# ESP-RC-Car_NEW.net
KiCad netlist of a schematic drawn in Altium Designer
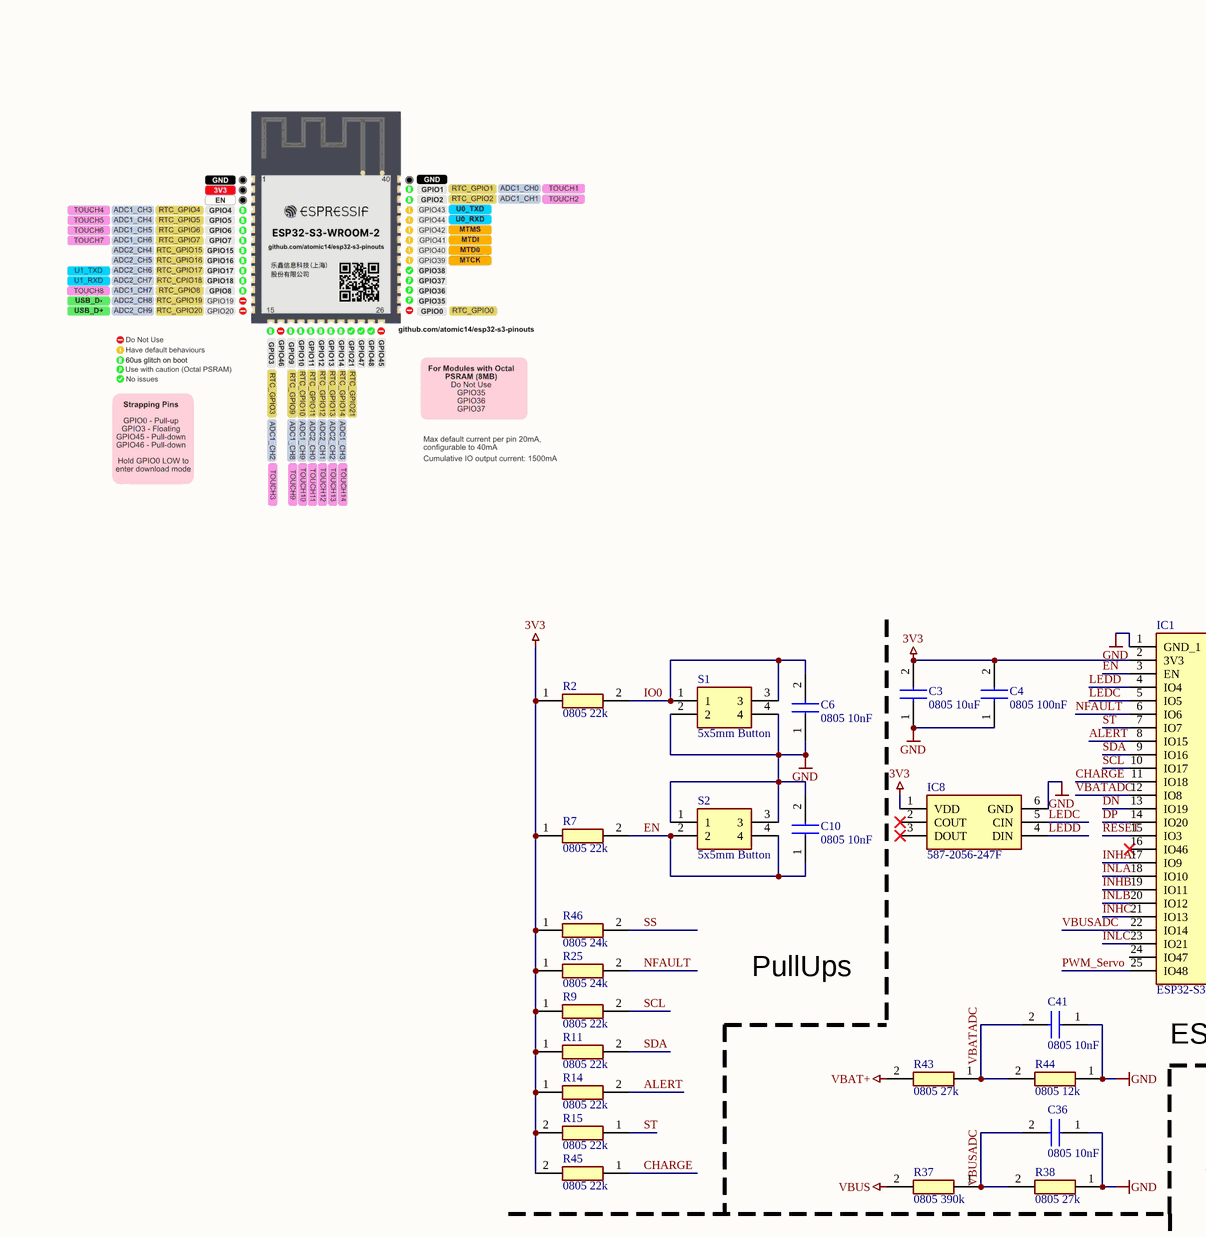
[diagram p0: ESP-RC-Car_NEW.SchDoc, top column 1 of 4]
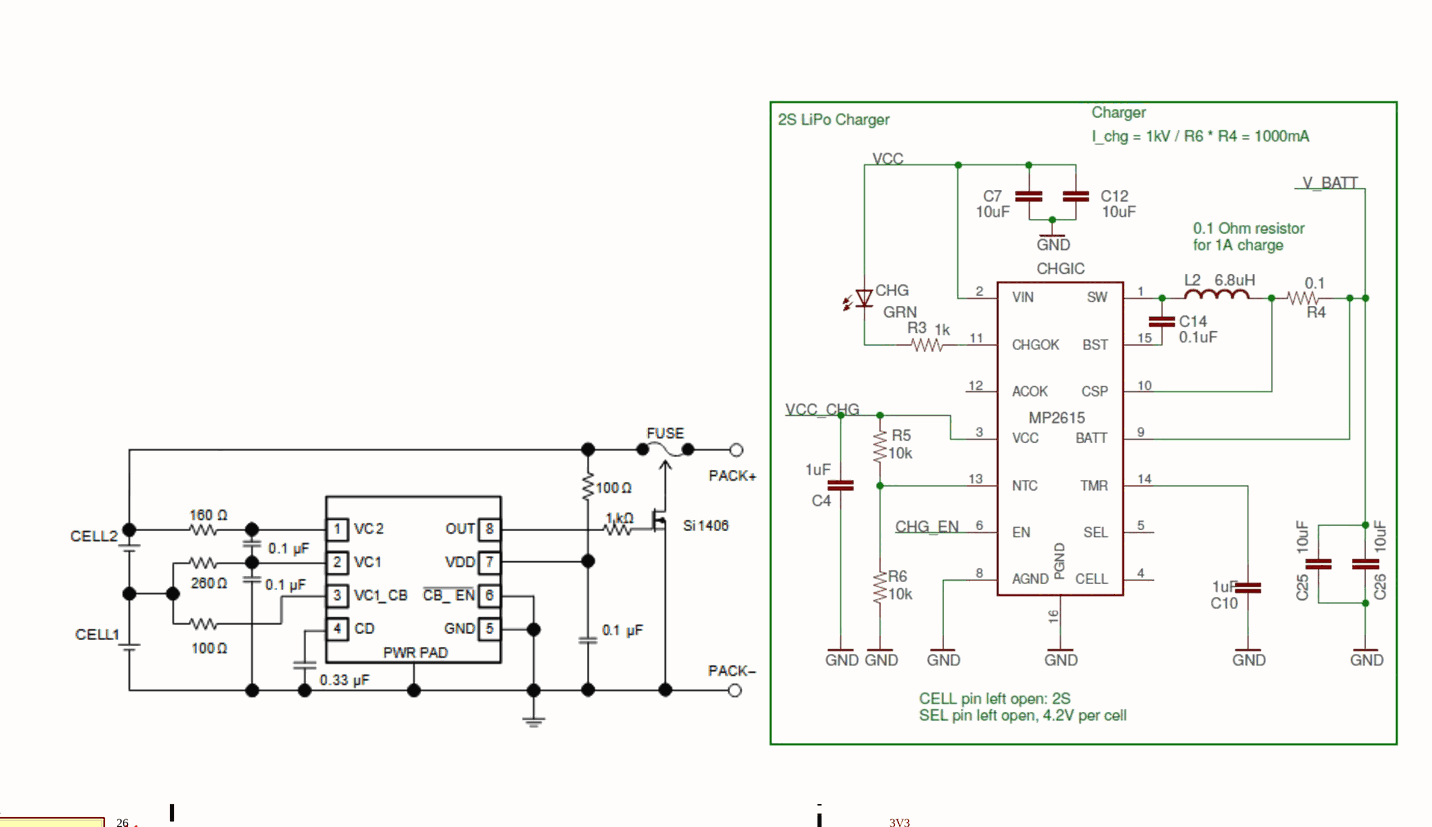
[diagram p1: ESP-RC-Car_NEW.SchDoc, top column 2 of 4]
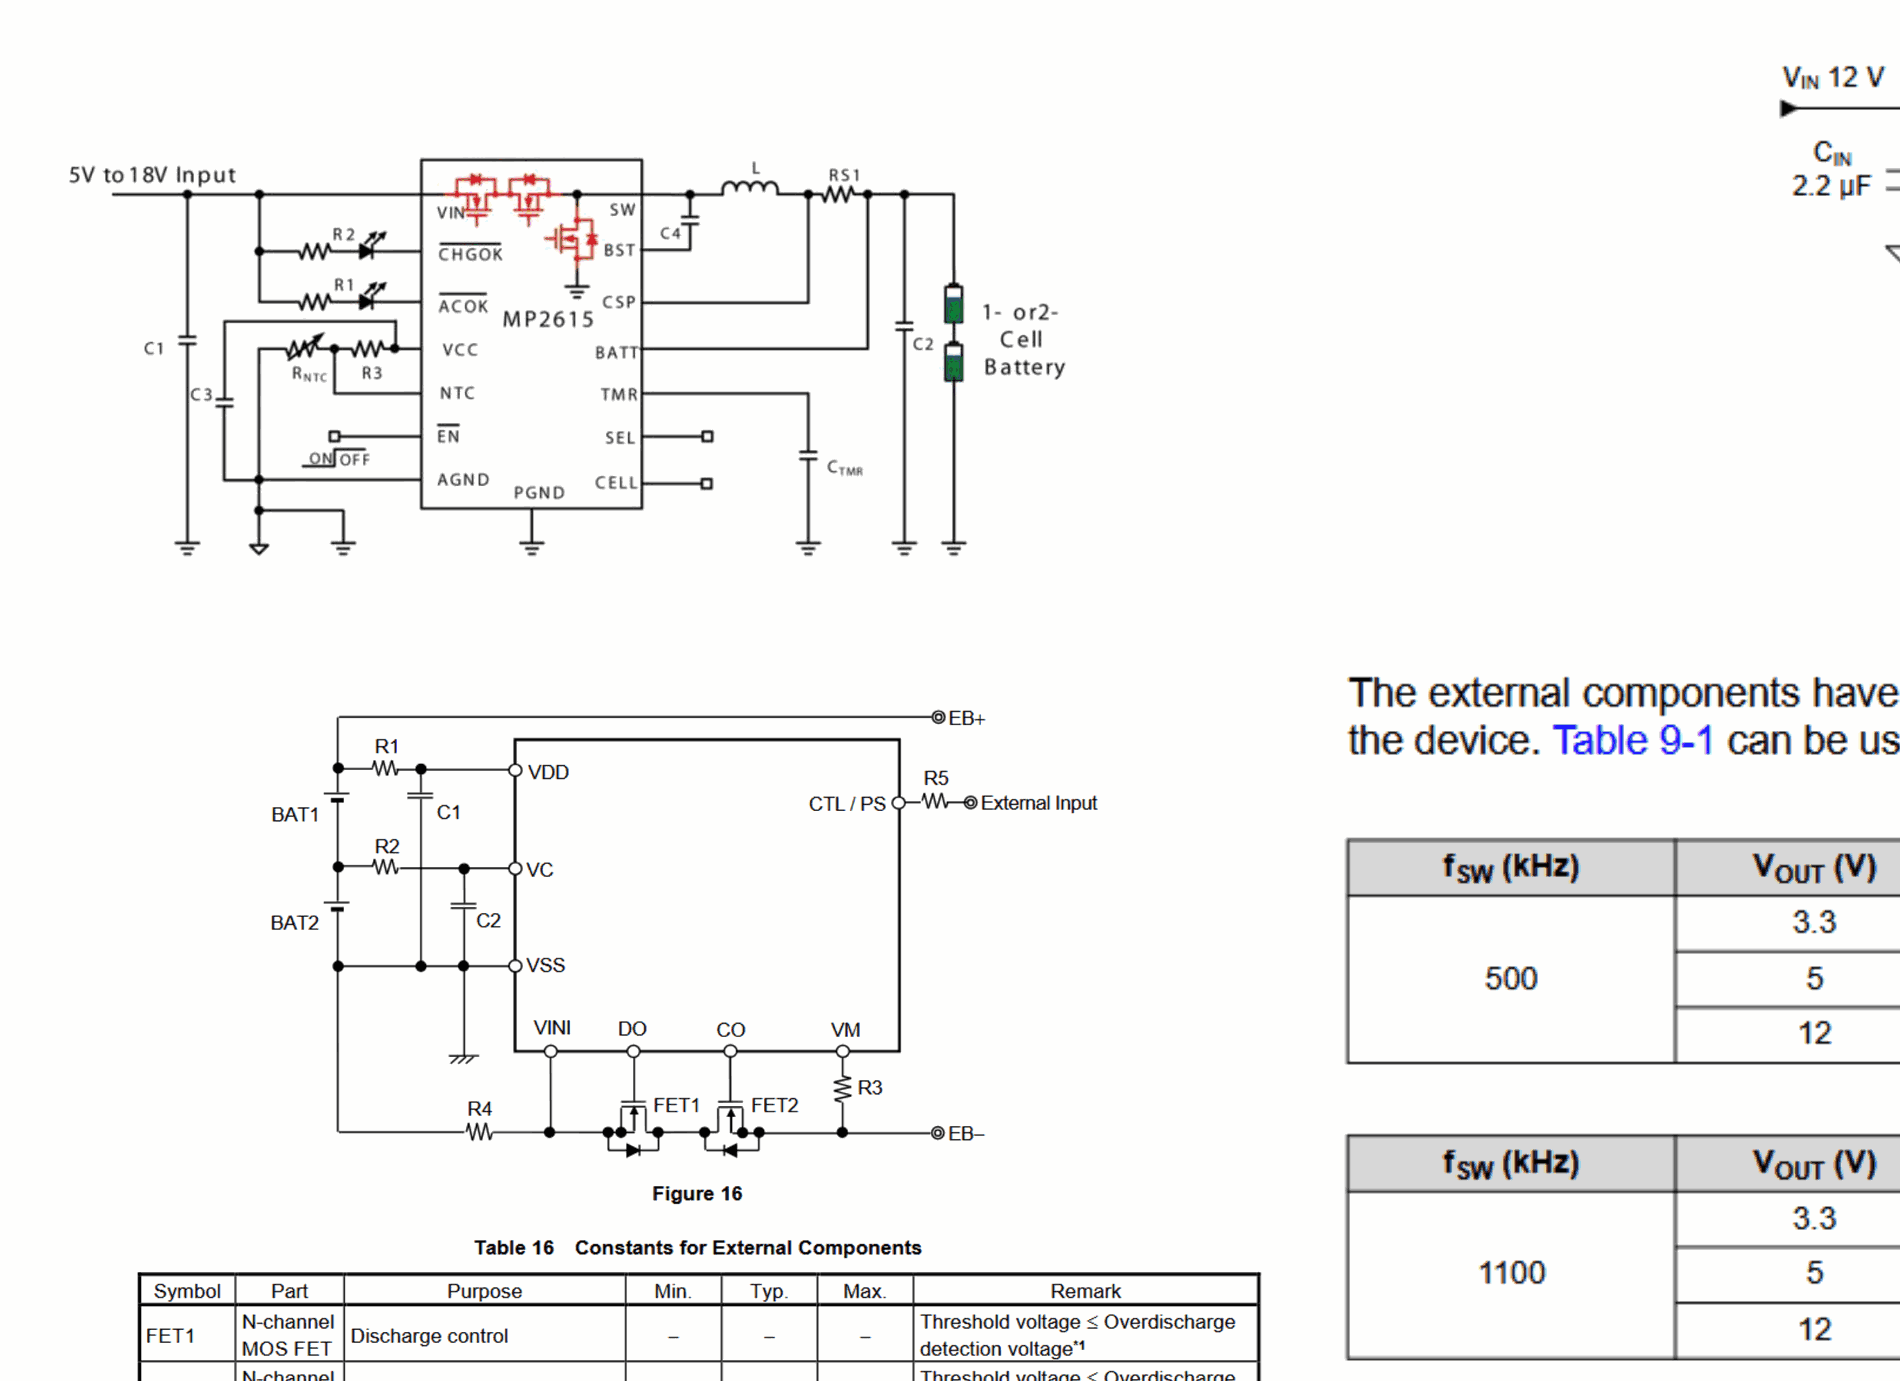
[diagram p2: ESP-RC-Car_NEW.SchDoc, top column 3 of 4]
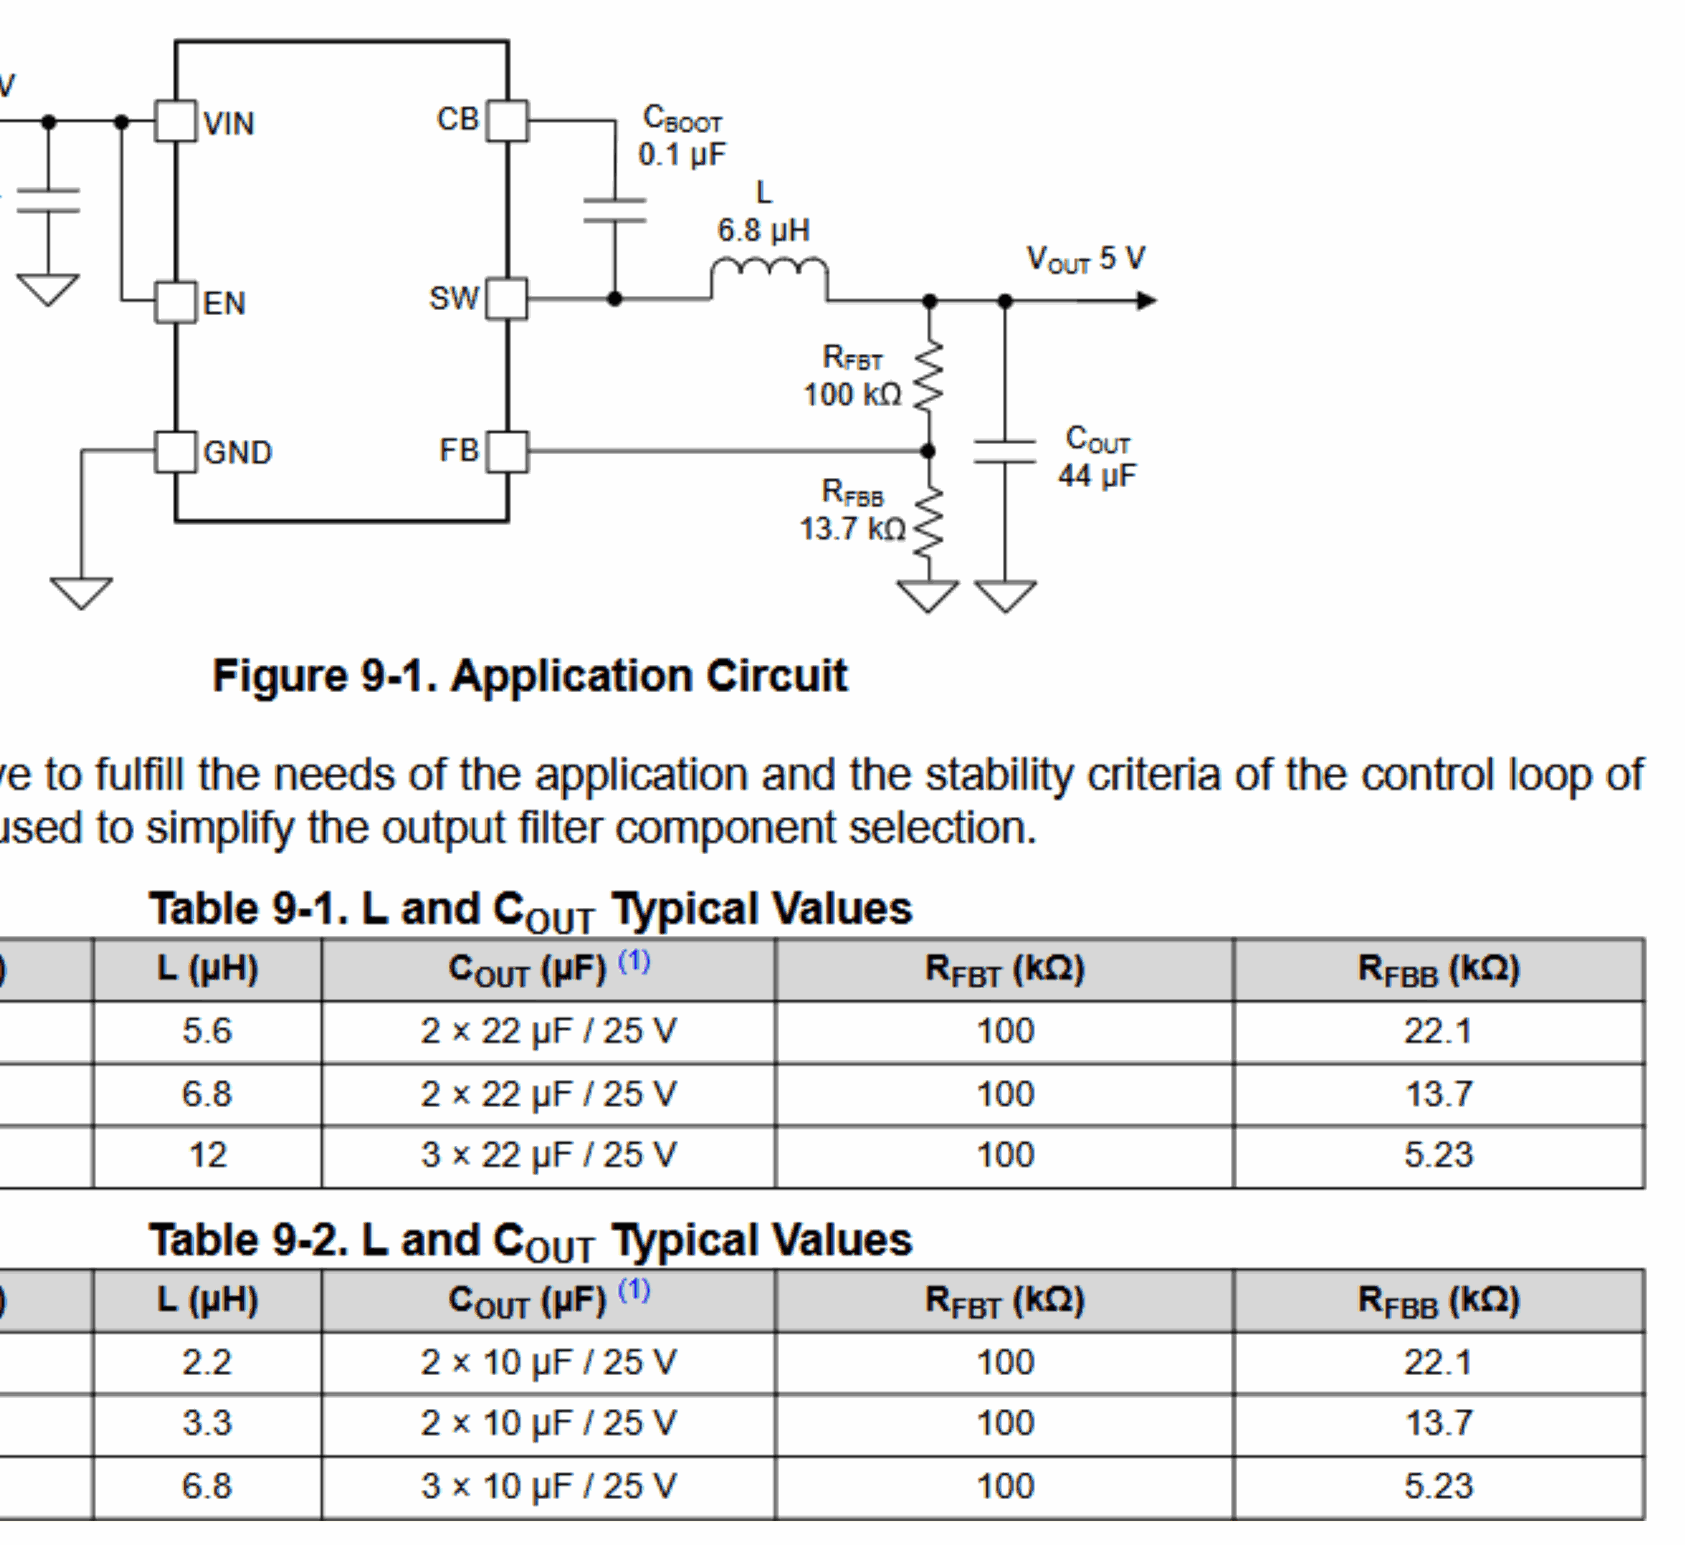
[diagram p3: ESP-RC-Car_NEW.SchDoc, top column 4 of 4]
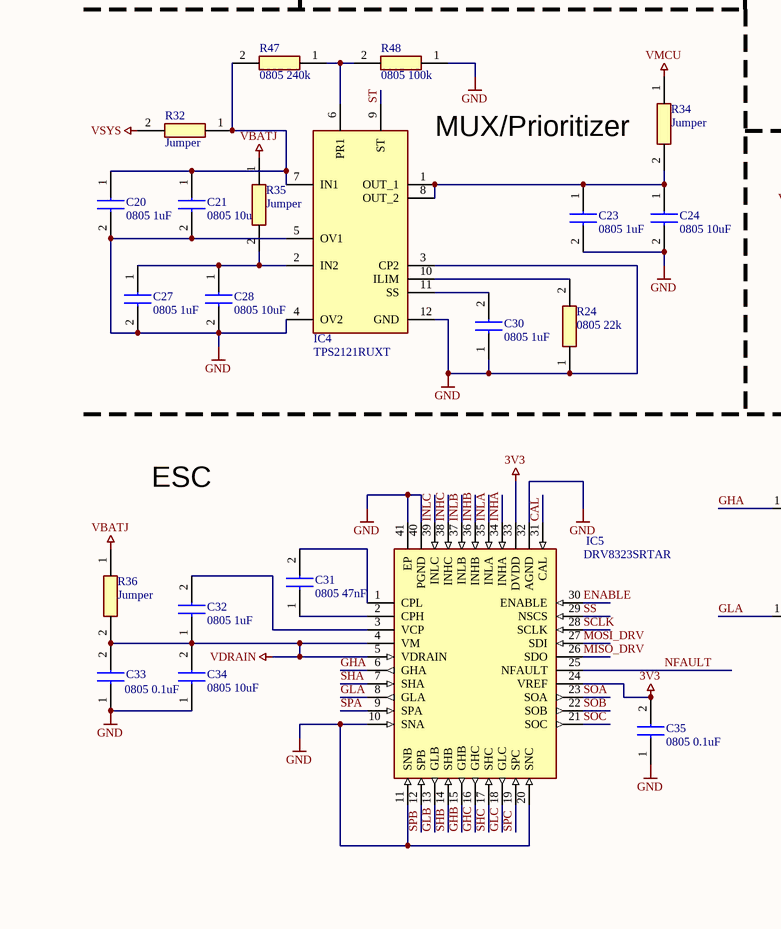
[diagram p4: ESP-RC-Car_NEW.SchDoc, bottom column 1 of 4]
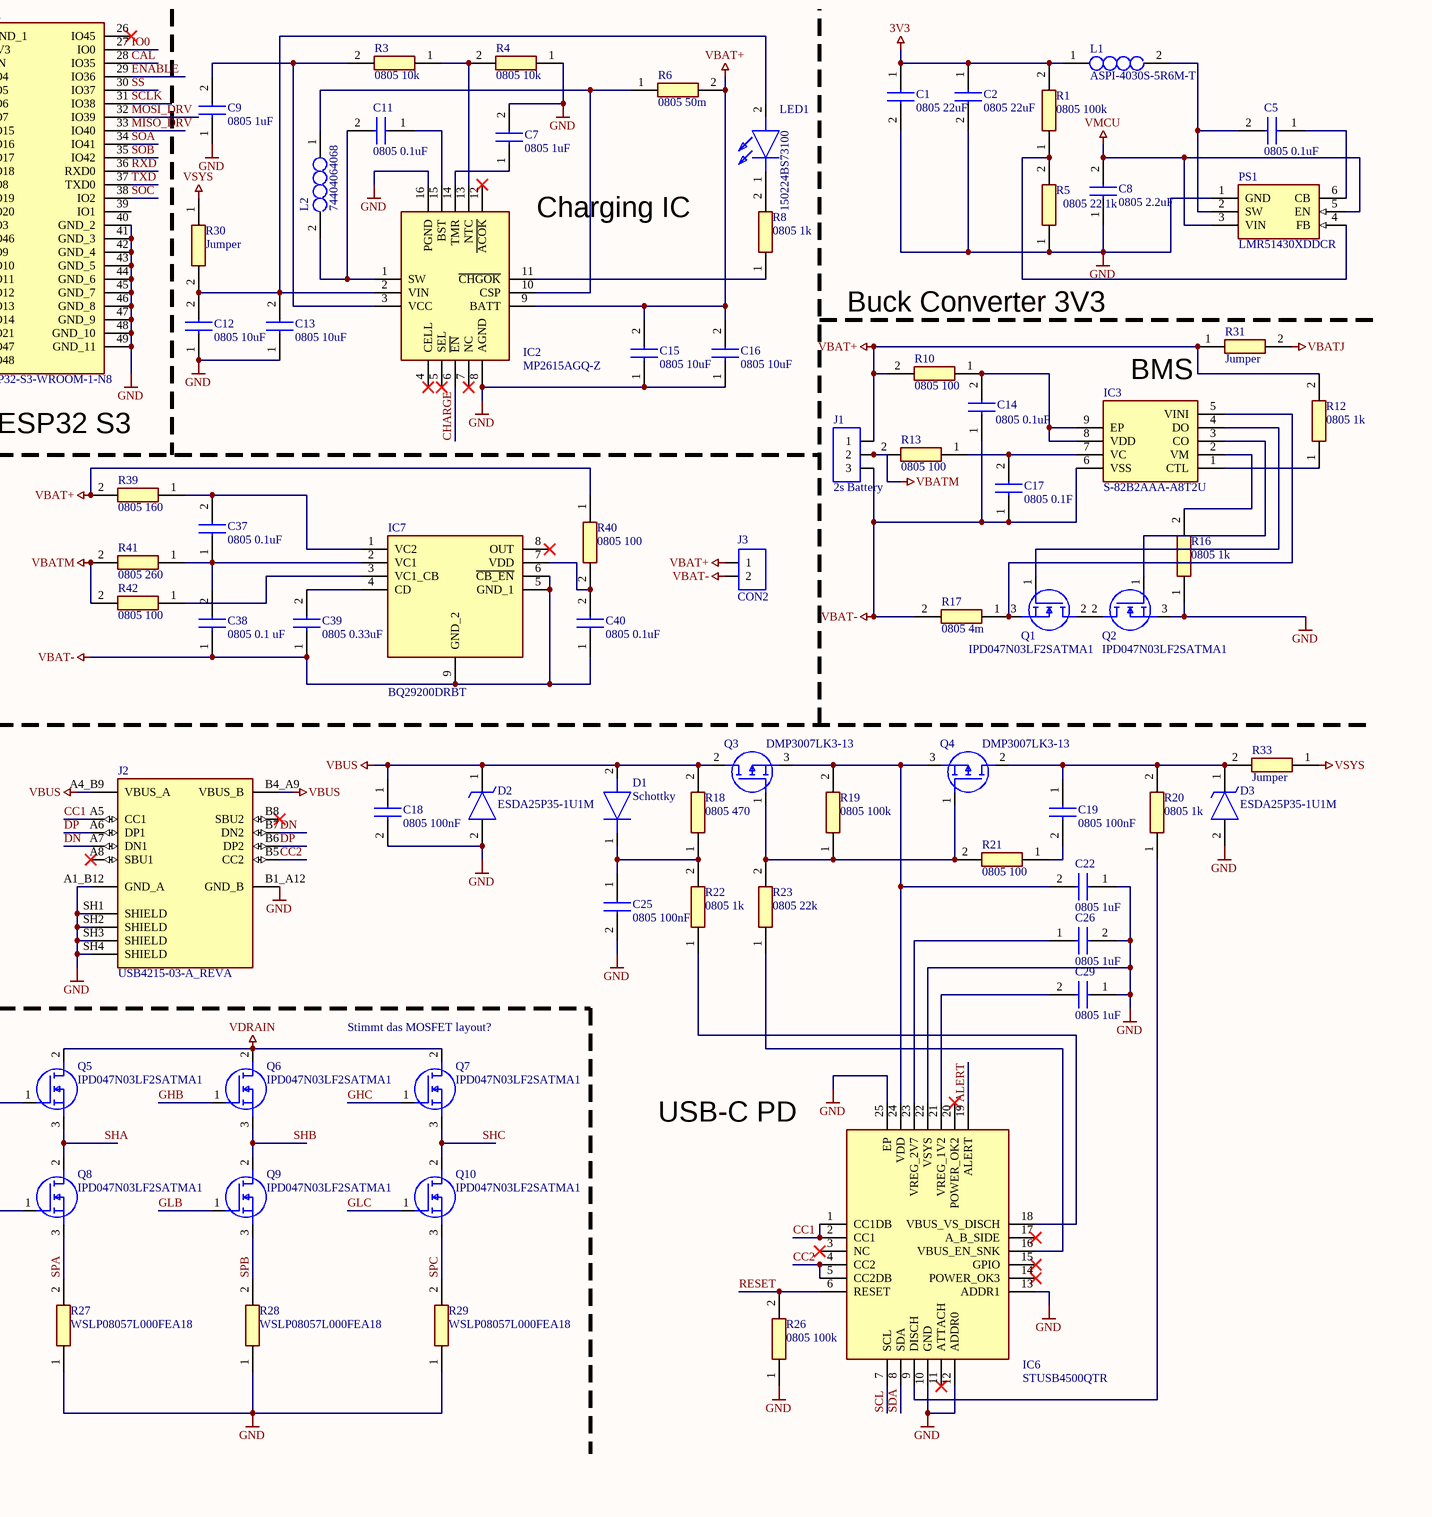
[diagram p5: ESP-RC-Car_NEW.SchDoc, bottom column 2 of 4]
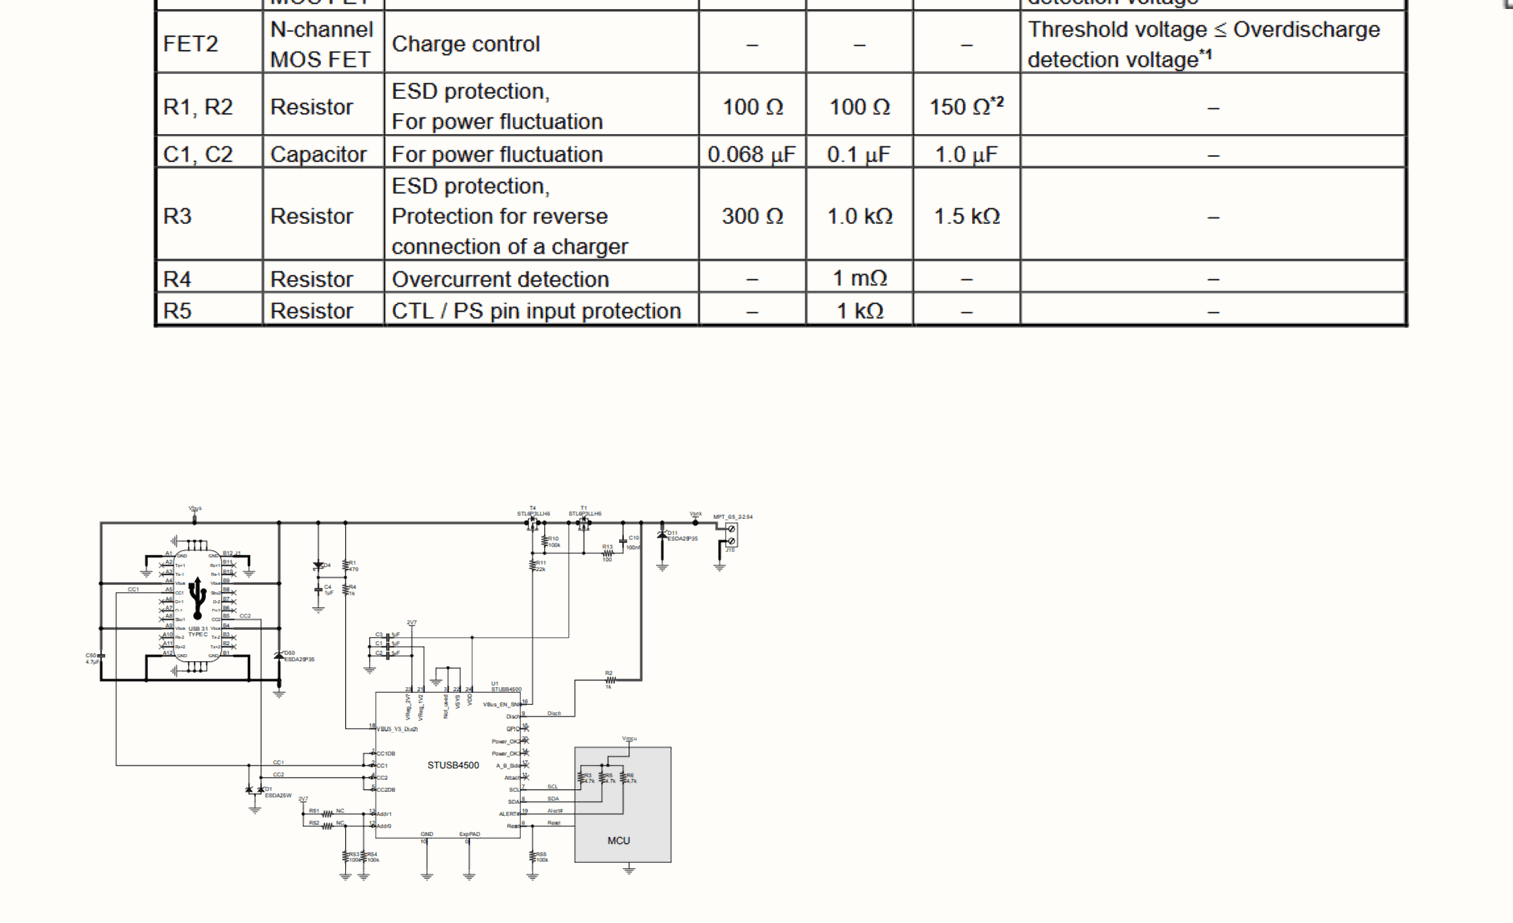
[diagram p6: ESP-RC-Car_NEW.SchDoc, bottom column 3 of 4]

(export (version "E")
  (design (tool "Eeschema 10.0.6"))
  (components
    (comp (ref "C1")
      (value "0805 22uF")
      (footprint "CAPC2012X94N")
      (description "Capacitor 25V")
      (fields
        (field (name "MANUFACTURER_PART_NUMBER") "08055A150JAT2A")
        (field (name "MOUSER PART NUMBER") "581-08055A150J")
      )
      (libsource (lib "*") (part "08055A150JAT2A"))
    )
    (comp (ref "C2")
      (value "0805 22uF")
      (footprint "CAPC2012X94N")
      (description "Capacitor 25V")
      (fields
        (field (name "MANUFACTURER_PART_NUMBER") "08055A150JAT2A")
        (field (name "MOUSER PART NUMBER") "581-08055A150J")
      )
      (libsource (lib "*") (part "08055A150JAT2A"))
    )
    (comp (ref "C3")
      (value "0805 10uF")
      (footprint "CAPC2012X94N")
      (description "Capacitor")
      (fields
        (field (name "MANUFACTURER_PART_NUMBER") "08055A150JAT2A")
        (field (name "MOUSER PART NUMBER") "581-08055A150J")
      )
      (libsource (lib "*") (part "08055A150JAT2A"))
    )
    (comp (ref "C4")
      (value "0805 100nF")
      (footprint "CAPC2012X94N")
      (description "Capacitor")
      (fields
        (field (name "MANUFACTURER_PART_NUMBER") "08055A150JAT2A")
        (field (name "MOUSER PART NUMBER") "581-08055A150J")
      )
      (libsource (lib "*") (part "08055A150JAT2A"))
    )
    (comp (ref "C5")
      (value "0805 0.1uF")
      (footprint "CAPC2012X94N")
      (description "Capacitor")
      (fields
        (field (name "MANUFACTURER_PART_NUMBER") "08055A150JAT2A")
        (field (name "MOUSER PART NUMBER") "581-08055A150J")
      )
      (libsource (lib "*") (part "08055A150JAT2A"))
    )
    (comp (ref "C6")
      (value "0805 10nF")
      (footprint "CAPC2012X94N")
      (description "Capacitor")
      (fields
        (field (name "MANUFACTURER_PART_NUMBER") "08055A150JAT2A")
        (field (name "MOUSER PART NUMBER") "581-08055A150J")
      )
      (libsource (lib "*") (part "08055A150JAT2A"))
    )
    (comp (ref "C7")
      (value "0805 1uF")
      (footprint "CAPC2012X94N")
      (description "Capacitor")
      (fields
        (field (name "MANUFACTURER_PART_NUMBER") "08055A150JAT2A")
        (field (name "MOUSER PART NUMBER") "581-08055A150J")
      )
      (libsource (lib "*") (part "08055A150JAT2A"))
    )
    (comp (ref "C8")
      (value "0805 2.2uF")
      (footprint "CAPC2012X94N")
      (description "Capacitor")
      (fields
        (field (name "MANUFACTURER_PART_NUMBER") "08055A150JAT2A")
        (field (name "MOUSER PART NUMBER") "581-08055A150J")
      )
      (libsource (lib "*") (part "08055A150JAT2A"))
    )
    (comp (ref "C9")
      (value "0805 1uF")
      (footprint "CAPC2012X94N")
      (description "Capacitor")
      (fields
        (field (name "MANUFACTURER_PART_NUMBER") "08055A150JAT2A")
        (field (name "MOUSER PART NUMBER") "581-08055A150J")
      )
      (libsource (lib "*") (part "08055A150JAT2A"))
    )
    (comp (ref "C10")
      (value "0805 10nF")
      (footprint "CAPC2012X94N")
      (description "Capacitor")
      (fields
        (field (name "MANUFACTURER_PART_NUMBER") "08055A150JAT2A")
        (field (name "MOUSER PART NUMBER") "581-08055A150J")
      )
      (libsource (lib "*") (part "08055A150JAT2A"))
    )
    (comp (ref "C11")
      (value "0805 0.1uF")
      (footprint "CAPC2012X94N")
      (description "Capacitor")
      (fields
        (field (name "MANUFACTURER_PART_NUMBER") "08055A150JAT2A")
        (field (name "MOUSER PART NUMBER") "581-08055A150J")
      )
      (libsource (lib "*") (part "08055A150JAT2A"))
    )
    (comp (ref "C12")
      (value "0805 10uF")
      (footprint "CAPC2012X94N")
      (description "Capacitor")
      (fields
        (field (name "MANUFACTURER_PART_NUMBER") "08055A150JAT2A")
        (field (name "MOUSER PART NUMBER") "581-08055A150J")
      )
      (libsource (lib "*") (part "08055A150JAT2A"))
    )
    (comp (ref "C13")
      (value "0805 10uF")
      (footprint "CAPC2012X94N")
      (description "Capacitor")
      (fields
        (field (name "MANUFACTURER_PART_NUMBER") "08055A150JAT2A")
        (field (name "MOUSER PART NUMBER") "581-08055A150J")
      )
      (libsource (lib "*") (part "08055A150JAT2A"))
    )
    (comp (ref "C14")
      (value "0805 0.1uF")
      (footprint "CAPC2012X94N")
      (description "Capacitor")
      (fields
        (field (name "MANUFACTURER_PART_NUMBER") "08055A150JAT2A")
        (field (name "MOUSER PART NUMBER") "581-08055A150J")
      )
      (libsource (lib "*") (part "08055A150JAT2A"))
    )
    (comp (ref "C15")
      (value "0805 10uF")
      (footprint "CAPC2012X94N")
      (description "Capacitor")
      (fields
        (field (name "MANUFACTURER_PART_NUMBER") "08055A150JAT2A")
        (field (name "MOUSER PART NUMBER") "581-08055A150J")
      )
      (libsource (lib "*") (part "08055A150JAT2A"))
    )
    (comp (ref "C16")
      (value "0805 10uF")
      (footprint "CAPC2012X94N")
      (description "Capacitor")
      (fields
        (field (name "MANUFACTURER_PART_NUMBER") "08055A150JAT2A")
        (field (name "MOUSER PART NUMBER") "581-08055A150J")
      )
      (libsource (lib "*") (part "08055A150JAT2A"))
    )
    (comp (ref "C17")
      (value "0805 0.1F")
      (footprint "CAPC2012X94N")
      (description "Capacitor")
      (fields
        (field (name "MANUFACTURER_PART_NUMBER") "08055A150JAT2A")
        (field (name "MOUSER PART NUMBER") "581-08055A150J")
      )
      (libsource (lib "*") (part "08055A150JAT2A"))
    )
    (comp (ref "C18")
      (value "0805 100nF")
      (footprint "CAPC2012X94N")
      (description "0805")
      (fields
        (field (name "MANUFACTURER_PART_NUMBER") "08055A150JAT2A")
        (field (name "MOUSER PART NUMBER") "581-08055A150J")
      )
      (libsource (lib "*") (part "08055A150JAT2A"))
    )
    (comp (ref "C19")
      (value "0805 100nF")
      (footprint "CAPC2012X94N")
      (description "0805")
      (fields
        (field (name "MANUFACTURER_PART_NUMBER") "08055A150JAT2A")
        (field (name "MOUSER PART NUMBER") "581-08055A150J")
      )
      (libsource (lib "*") (part "08055A150JAT2A"))
    )
    (comp (ref "C20")
      (value "0805 1uF")
      (footprint "CAPC2012X94N")
      (description "0805")
      (fields
        (field (name "MANUFACTURER_PART_NUMBER") "08055A150JAT2A")
        (field (name "MOUSER PART NUMBER") "581-08055A150J")
      )
      (libsource (lib "*") (part "08055A150JAT2A"))
    )
    (comp (ref "C21")
      (value "0805 10uF")
      (footprint "CAPC2012X94N")
      (description "0805")
      (fields
        (field (name "MANUFACTURER_PART_NUMBER") "08055A150JAT2A")
        (field (name "MOUSER PART NUMBER") "581-08055A150J")
      )
      (libsource (lib "*") (part "08055A150JAT2A"))
    )
    (comp (ref "C22")
      (value "0805 1uF")
      (footprint "CAPC2012X94N")
      (description "0805")
      (fields
        (field (name "MANUFACTURER_PART_NUMBER") "08055A150JAT2A")
        (field (name "MOUSER PART NUMBER") "581-08055A150J")
      )
      (libsource (lib "*") (part "08055A150JAT2A"))
    )
    (comp (ref "C23")
      (value "0805 1uF")
      (footprint "CAPC2012X94N")
      (description "0805")
      (fields
        (field (name "MANUFACTURER_PART_NUMBER") "08055A150JAT2A")
        (field (name "MOUSER PART NUMBER") "581-08055A150J")
      )
      (libsource (lib "*") (part "08055A150JAT2A"))
    )
    (comp (ref "C24")
      (value "0805 10uF")
      (footprint "CAPC2012X94N")
      (description "0805")
      (fields
        (field (name "MANUFACTURER_PART_NUMBER") "08055A150JAT2A")
        (field (name "MOUSER PART NUMBER") "581-08055A150J")
      )
      (libsource (lib "*") (part "08055A150JAT2A"))
    )
    (comp (ref "C25")
      (value "0805 100nF")
      (footprint "CAPC2012X94N")
      (description "0805")
      (fields
        (field (name "MANUFACTURER_PART_NUMBER") "08055A150JAT2A")
        (field (name "MOUSER PART NUMBER") "581-08055A150J")
      )
      (libsource (lib "*") (part "08055A150JAT2A"))
    )
    (comp (ref "C26")
      (value "0805 1uF")
      (footprint "CAPC2012X94N")
      (description "0805")
      (fields
        (field (name "MANUFACTURER_PART_NUMBER") "08055A150JAT2A")
        (field (name "MOUSER PART NUMBER") "581-08055A150J")
      )
      (libsource (lib "*") (part "08055A150JAT2A"))
    )
    (comp (ref "C27")
      (value "0805 1uF")
      (footprint "CAPC2012X94N")
      (description "0805")
      (fields
        (field (name "MANUFACTURER_PART_NUMBER") "08055A150JAT2A")
        (field (name "MOUSER PART NUMBER") "581-08055A150J")
      )
      (libsource (lib "*") (part "08055A150JAT2A"))
    )
    (comp (ref "C28")
      (value "0805 10uF")
      (footprint "CAPC2012X94N")
      (description "0805")
      (fields
        (field (name "MANUFACTURER_PART_NUMBER") "08055A150JAT2A")
        (field (name "MOUSER PART NUMBER") "581-08055A150J")
      )
      (libsource (lib "*") (part "08055A150JAT2A"))
    )
    (comp (ref "C29")
      (value "0805 1uF")
      (footprint "CAPC2012X94N")
      (description "0805")
      (fields
        (field (name "MANUFACTURER_PART_NUMBER") "08055A150JAT2A")
        (field (name "MOUSER PART NUMBER") "581-08055A150J")
      )
      (libsource (lib "*") (part "08055A150JAT2A"))
    )
    (comp (ref "C30")
      (value "0805 1uF")
      (footprint "CAPC2012X94N")
      (description "0805")
      (fields
        (field (name "MANUFACTURER_PART_NUMBER") "08055A150JAT2A")
        (field (name "MOUSER PART NUMBER") "581-08055A150J")
      )
      (libsource (lib "*") (part "08055A150JAT2A"))
    )
    (comp (ref "C31")
      (value "0805 47nF")
      (footprint "CAPC2012X94N")
      (description "0805")
      (fields
        (field (name "MANUFACTURER_PART_NUMBER") "08055A150JAT2A")
        (field (name "MOUSER PART NUMBER") "581-08055A150J")
      )
      (libsource (lib "*") (part "08055A150JAT2A"))
    )
    (comp (ref "C32")
      (value "0805 1uF")
      (footprint "CAPC2012X94N")
      (description "0805 16V X5R/X7R")
      (fields
        (field (name "MANUFACTURER_PART_NUMBER") "08055A150JAT2A")
        (field (name "MOUSER PART NUMBER") "581-08055A150J")
      )
      (libsource (lib "*") (part "08055A150JAT2A"))
    )
    (comp (ref "C33")
      (value "0805 0.1uF")
      (footprint "CAPC2012X94N")
      (description "0805 VM rated")
      (fields
        (field (name "MANUFACTURER_PART_NUMBER") "08055A150JAT2A")
        (field (name "MOUSER PART NUMBER") "581-08055A150J")
      )
      (libsource (lib "*") (part "08055A150JAT2A"))
    )
    (comp (ref "C34")
      (value "0805 10uF")
      (footprint "CAPC2012X94N")
      (description "0805")
      (fields
        (field (name "MANUFACTURER_PART_NUMBER") "08055A150JAT2A")
        (field (name "MOUSER PART NUMBER") "581-08055A150J")
      )
      (libsource (lib "*") (part "08055A150JAT2A"))
    )
    (comp (ref "C35")
      (value "0805 0.1uF")
      (footprint "CAPC2012X94N")
      (description "0805")
      (fields
        (field (name "MANUFACTURER_PART_NUMBER") "08055A150JAT2A")
        (field (name "MOUSER PART NUMBER") "581-08055A150J")
      )
      (libsource (lib "*") (part "08055A150JAT2A"))
    )
    (comp (ref "C36")
      (value "0805 10nF")
      (footprint "CAPC2012X94N")
      (description "Capacitor")
      (fields
        (field (name "MANUFACTURER_PART_NUMBER") "08055A150JAT2A")
        (field (name "MOUSER PART NUMBER") "581-08055A150J")
      )
      (libsource (lib "*") (part "08055A150JAT2A"))
    )
    (comp (ref "C37")
      (value "0805 0.1uF")
      (footprint "CAPC2012X94N")
      (description "Capacitor")
      (fields
        (field (name "MANUFACTURER_PART_NUMBER") "08055A150JAT2A")
        (field (name "MOUSER PART NUMBER") "581-08055A150J")
      )
      (libsource (lib "*") (part "08055A150JAT2A"))
    )
    (comp (ref "C38")
      (value "0805 0.1 uF")
      (footprint "CAPC2012X94N")
      (description "Capacitor")
      (fields
        (field (name "MANUFACTURER_PART_NUMBER") "08055A150JAT2A")
        (field (name "MOUSER PART NUMBER") "581-08055A150J")
      )
      (libsource (lib "*") (part "08055A150JAT2A"))
    )
    (comp (ref "C39")
      (value "0805 0.33uF")
      (footprint "CAPC2012X94N")
      (description "Capacitor")
      (fields
        (field (name "MANUFACTURER_PART_NUMBER") "08055A150JAT2A")
        (field (name "MOUSER PART NUMBER") "581-08055A150J")
      )
      (libsource (lib "*") (part "08055A150JAT2A"))
    )
    (comp (ref "C40")
      (value "0805 0.1uF")
      (footprint "CAPC2012X94N")
      (description "Capacitor")
      (fields
        (field (name "MANUFACTURER_PART_NUMBER") "08055A150JAT2A")
        (field (name "MOUSER PART NUMBER") "581-08055A150J")
      )
      (libsource (lib "*") (part "08055A150JAT2A"))
    )
    (comp (ref "C41")
      (value "0805 10nF")
      (footprint "CAPC2012X94N")
      (description "Capacitor")
      (fields
        (field (name "MANUFACTURER_PART_NUMBER") "08055A150JAT2A")
        (field (name "MOUSER PART NUMBER") "581-08055A150J")
      )
      (libsource (lib "*") (part "08055A150JAT2A"))
    )
    (comp (ref "D1")
      (value "Schottky")
      (footprint "SODFL3517X110N")
      (description "Schottky Diode")
      (fields (field (name "MANUFACTURER_PART_NUMBER") "PMEG3010ER"))
      (libsource (lib "*") (part "PMEG3010ER"))
    )
    (comp (ref "D2")
      (value "ESDA25P35-1U1M")
      (footprint "ESDA25P351U1M")
      (description "TVS Diode (Uni-directional)")
      (fields (field (name "MOUSER PART NUMBER") "511-ESDA25P35-1U1M"))
      (libsource (lib "*") (part "ESDA25P35-1U1M"))
    )
    (comp (ref "D3")
      (value "ESDA25P35-1U1M")
      (footprint "ESDA25P351U1M")
      (description "TVS Diode (Uni-directional)")
      (fields (field (name "MOUSER PART NUMBER") "511-ESDA25P35-1U1M"))
      (libsource (lib "*") (part "ESDA25P35-1U1M"))
    )
    (comp (ref "IC1")
      (value "ESP32-S3-WROOM-1-N8")
      (footprint "ESP32S3WROOM1N8R2")
      (description "Integrated Circuit")
      (fields (field (name "MOUSER PART NUMBER") "356-ESP32-S3WROOM1N8"))
      (libsource (lib "*") (part "ESP32-S3-WROOM-1-N8"))
    )
    (comp (ref "IC2")
      (value "MP2615AGQ-Z")
      (footprint "MP2615AGQZ")
      (description "Integrated Circuit")
      (fields (field (name "MOUSER PART NUMBER") "946-MP2615AGQ-Z"))
      (libsource (lib "*") (part "MP2615AGQ-Z"))
    )
    (comp (ref "IC3")
      (value "S-82B2AAA-A8T2U")
      (footprint "S82B2AAAA8T2U")
      (description "Integrated Circuit")
      (fields (field (name "MOUSER PART NUMBER") "628-S-82B2AAA-A8T2U"))
      (libsource (lib "*") (part "S-82B2AAA-A8T2U"))
    )
    (comp (ref "IC4")
      (value "TPS2121RUXT")
      (footprint "TPS2121RUXT")
      (description "Integrated Circuit")
      (fields (field (name "MOUSER PART NUMBER") "595-TPS2121RUXT"))
      (libsource (lib "*") (part "TPS2121RUXT"))
    )
    (comp (ref "IC5")
      (value "DRV8323SRTAR")
      (footprint "QFN50P600X600X80-41N-D")
      (description "Integrated Circuit")
      (fields (field (name "MOUSER PART NUMBER") "595-DRV8323SRTAR"))
      (libsource (lib "lib") (part "DRV8323SRTAR"))
    )
    (comp (ref "IC6")
      (value "STUSB4500QTR")
      (footprint "QFN50P400X400X100-25N-D")
      (description "Integrated Circuit")
      (fields (field (name "MOUSER PART NUMBER") "511-STUSB4500QTR"))
      (libsource (lib "*") (part "STUSB4500QTR"))
    )
    (comp (ref "IC7")
      (value "BQ29200DRBT")
      (footprint "SON65P300X300X100-9N-D")
      (description "Integrated Circuit")
      (fields (field (name "MOUSER PART NUMBER") "595-BQ29200DRBT"))
      (libsource (lib "*") (part "BQ29200DRBT"))
    )
    (comp (ref "IC8")
      (value "587-2056-247F")
      (footprint "lib:5872056247F")
      (description "Integrated Circuit")
      (libsource (lib "*") (part "587-2056-247F"))
    )
    (comp (ref "J1")
      (value "2s Battery")
      (footprint "Sip-3")
      (description "Stecker")
      (libsource (lib "lib") (part "CON3"))
    )
    (comp (ref "J2")
      (value "USB4215-03-A_REVA")
      (footprint "GCT_USB4215-03-A_REVA")
      (fields (field (name "MF") "Global Connector Technology") (field (name "MP") "USB4215-03-A"))
      (libsource (lib "lib") (part "USB4215-03-A_REVA"))
    )
    (comp (ref "J3")
      (value "CON2")
      (footprint "SIP-2")
      (description "Stecker")
      (libsource (lib "lib") (part "CON2"))
    )
    (comp (ref "L1")
      (value "ASPI-4030S-5R6M-T")
      (footprint "ASPI-4030S")
      (description "Inductor")
      (fields (field (name "MOUSER PART NUMBER") "815-ASPI-4030S-5R6MT"))
      (libsource (lib "*") (part "ASPI-4030S-5R6M-T"))
    )
    (comp (ref "L2")
      (value "74404064068")
      (footprint "INDPM6060X450N")
      (description "Inductor")
      (fields (field (name "MOUSER PART NUMBER") "710-74404064068"))
      (libsource (lib "*") (part "74404064068"))
    )
    (comp (ref "LED1")
      (value "150224BS73100")
      (footprint "150224BS73100")
      (description "LED")
      (fields (field (name "MOUSER PART NUMBER") "710-150224BS73100"))
      (libsource (lib "*") (part "150224BS73100"))
    )
    (comp (ref "PS1")
      (value "LMR51430XDDCR")
      (footprint "SOT95P280X110-6N")
      (description "Power Supply 500kHz")
      (fields (field (name "MOUSER PART NUMBER") "595-LMR51430XDDCR"))
      (libsource (lib "*") (part "LMR51430XDDCR"))
    )
    (comp (ref "Q1")
      (value "IPD047N03LF2SATMA1")
      (footprint "IPD047N03LF2SATMA1")
      (description "MOSFET (N-Channel)")
      (fields (field (name "MOUSER PART NUMBER") "726-IPD047N03LF2SATM"))
      (libsource (lib "*") (part "IPD047N03LF2SATMA1"))
    )
    (comp (ref "Q2")
      (value "IPD047N03LF2SATMA1")
      (footprint "IPD047N03LF2SATMA1")
      (description "MOSFET (N-Channel)")
      (fields (field (name "MOUSER PART NUMBER") "726-IPD047N03LF2SATM"))
      (libsource (lib "*") (part "IPD047N03LF2SATMA1"))
    )
    (comp (ref "Q3")
      (value "DMP3007LK3-13")
      (footprint "DMP3007LK313")
      (description "MOSFET (P-Channel)")
      (fields (field (name "MOUSER PART NUMBER") "621-DMP3007LK3-13"))
      (libsource (lib "*") (part "DMP3007LK3-13"))
    )
    (comp (ref "Q4")
      (value "DMP3007LK3-13")
      (footprint "DMP3007LK313")
      (description "MOSFET (P-Channel)")
      (fields (field (name "MOUSER PART NUMBER") "621-DMP3007LK3-13"))
      (libsource (lib "*") (part "DMP3007LK3-13"))
    )
    (comp (ref "Q5")
      (value "IPD047N03LF2SATMA1")
      (footprint "IPD047N03LF2SATMA1")
      (description "MOSFET (N-Channel)")
      (fields (field (name "MOUSER PART NUMBER") "726-IPD047N03LF2SATM"))
      (libsource (lib "*") (part "IPD047N03LF2SATMA1"))
    )
    (comp (ref "Q6")
      (value "IPD047N03LF2SATMA1")
      (footprint "IPD047N03LF2SATMA1")
      (description "MOSFET (N-Channel)")
      (fields (field (name "MOUSER PART NUMBER") "726-IPD047N03LF2SATM"))
      (libsource (lib "*") (part "IPD047N03LF2SATMA1"))
    )
    (comp (ref "Q7")
      (value "IPD047N03LF2SATMA1")
      (footprint "IPD047N03LF2SATMA1")
      (description "MOSFET (N-Channel)")
      (fields (field (name "MOUSER PART NUMBER") "726-IPD047N03LF2SATM"))
      (libsource (lib "*") (part "IPD047N03LF2SATMA1"))
    )
    (comp (ref "Q8")
      (value "IPD047N03LF2SATMA1")
      (footprint "IPD047N03LF2SATMA1")
      (description "MOSFET (N-Channel)")
      (fields (field (name "MOUSER PART NUMBER") "726-IPD047N03LF2SATM"))
      (libsource (lib "*") (part "IPD047N03LF2SATMA1"))
    )
    (comp (ref "Q9")
      (value "IPD047N03LF2SATMA1")
      (footprint "IPD047N03LF2SATMA1")
      (description "MOSFET (N-Channel)")
      (fields (field (name "MOUSER PART NUMBER") "726-IPD047N03LF2SATM"))
      (libsource (lib "*") (part "IPD047N03LF2SATMA1"))
    )
    (comp (ref "Q10")
      (value "IPD047N03LF2SATMA1")
      (footprint "IPD047N03LF2SATMA1")
      (description "MOSFET (N-Channel)")
      (fields (field (name "MOUSER PART NUMBER") "726-IPD047N03LF2SATM"))
      (libsource (lib "*") (part "IPD047N03LF2SATMA1"))
    )
    (comp (ref "R1")
      (value "0805 100k")
      (footprint "RESC2012X65N")
      (description "Resistor low tolerance")
      (fields (field (name "MANUFACTURER_PART_NUMBER") "CPF0805B102RE1"))
      (libsource (lib "") (part "CPF0805B102RE1_3"))
    )
    (comp (ref "R2")
      (value "0805 22k")
      (footprint "RESC2012X65N")
      (description "Resistor")
      (fields (field (name "MANUFACTURER_PART_NUMBER") "CPF0805B102RE1"))
      (libsource (lib "*") (part "CPF0805B102RE1"))
    )
    (comp (ref "R3")
      (value "0805 10k")
      (footprint "RESC2012X65N")
      (description "Resistor low tolerance")
      (fields (field (name "MANUFACTURER_PART_NUMBER") "CPF0805B102RE1"))
      (libsource (lib "") (part "CPF0805B102RE1_1"))
    )
    (comp (ref "R4")
      (value "0805 10k")
      (footprint "RESC2012X65N")
      (description "Resistor low tolerance")
      (fields (field (name "MANUFACTURER_PART_NUMBER") "CPF0805B102RE1"))
      (libsource (lib "") (part "CPF0805B102RE1_1"))
    )
    (comp (ref "R5")
      (value "0805 22.1k")
      (footprint "RESC2012X65N")
      (description "Resistor low tolerance")
      (fields (field (name "MANUFACTURER_PART_NUMBER") "CPF0805B102RE1"))
      (libsource (lib "") (part "CPF0805B102RE1_3"))
    )
    (comp (ref "R6")
      (value "0805 50m")
      (footprint "RESC2012X65N")
      (description "Resistor low tolerance")
      (fields (field (name "MANUFACTURER_PART_NUMBER") "CPF0805B102RE1"))
      (libsource (lib "*") (part "CPF0805B102RE1"))
    )
    (comp (ref "R7")
      (value "0805 22k")
      (footprint "RESC2012X65N")
      (description "Resistor")
      (fields (field (name "MANUFACTURER_PART_NUMBER") "CPF0805B102RE1"))
      (libsource (lib "*") (part "CPF0805B102RE1"))
    )
    (comp (ref "R8")
      (value "0805 1k")
      (footprint "RESC2012X65N")
      (description "Resistor low tolerance")
      (fields (field (name "MANUFACTURER_PART_NUMBER") "CPF0805B102RE1"))
      (libsource (lib "") (part "CPF0805B102RE1_3"))
    )
    (comp (ref "R9")
      (value "0805 22k")
      (footprint "RESC2012X65N")
      (description "Resistor")
      (fields (field (name "MANUFACTURER_PART_NUMBER") "CPF0805B102RE1"))
      (libsource (lib "*") (part "CPF0805B102RE1"))
    )
    (comp (ref "R10")
      (value "0805 100")
      (footprint "RESC2012X65N")
      (description "Resistor low tolerance")
      (fields (field (name "MANUFACTURER_PART_NUMBER") "CPF0805B102RE1"))
      (libsource (lib "") (part "CPF0805B102RE1_1"))
    )
    (comp (ref "R11")
      (value "0805 22k")
      (footprint "RESC2012X65N")
      (description "Resistor")
      (fields (field (name "MANUFACTURER_PART_NUMBER") "CPF0805B102RE1"))
      (libsource (lib "*") (part "CPF0805B102RE1"))
    )
    (comp (ref "R12")
      (value "0805 1k")
      (footprint "RESC2012X65N")
      (description "Resistor low tolerance")
      (fields (field (name "MANUFACTURER_PART_NUMBER") "CPF0805B102RE1"))
      (libsource (lib "") (part "CPF0805B102RE1_3"))
    )
    (comp (ref "R13")
      (value "0805 100")
      (footprint "RESC2012X65N")
      (description "Resistor low tolerance")
      (fields (field (name "MANUFACTURER_PART_NUMBER") "CPF0805B102RE1"))
      (libsource (lib "") (part "CPF0805B102RE1_1"))
    )
    (comp (ref "R14")
      (value "0805 22k")
      (footprint "RESC2012X65N")
      (description "Resistor")
      (fields (field (name "MANUFACTURER_PART_NUMBER") "CPF0805B102RE1"))
      (libsource (lib "*") (part "CPF0805B102RE1"))
    )
    (comp (ref "R15")
      (value "0805 22k")
      (footprint "RESC2012X65N")
      (description "Resistor")
      (fields (field (name "MANUFACTURER_PART_NUMBER") "CPF0805B102RE1"))
      (libsource (lib "") (part "CPF0805B102RE1_1"))
    )
    (comp (ref "R16")
      (value "0805 1k")
      (footprint "RESC2012X65N")
      (description "Resistor low tolerance")
      (fields (field (name "MANUFACTURER_PART_NUMBER") "CPF0805B102RE1"))
      (libsource (lib "") (part "CPF0805B102RE1_3"))
    )
    (comp (ref "R17")
      (value "0805 4m")
      (footprint "RESC2012X65N")
      (description "Resistor low tolerance")
      (fields (field (name "MANUFACTURER_PART_NUMBER") "CPF0805B102RE1"))
      (libsource (lib "") (part "CPF0805B102RE1_1"))
    )
    (comp (ref "R18")
      (value "0805 470")
      (footprint "RESC2012X65N")
      (description "Resistor")
      (fields (field (name "MANUFACTURER_PART_NUMBER") "CPF0805B102RE1"))
      (libsource (lib "") (part "CPF0805B102RE1_3"))
    )
    (comp (ref "R19")
      (value "0805 100k")
      (footprint "RESC2012X65N")
      (description "Resistor")
      (fields (field (name "MANUFACTURER_PART_NUMBER") "CPF0805B102RE1"))
      (libsource (lib "") (part "CPF0805B102RE1_3"))
    )
    (comp (ref "R20")
      (value "0805 1k")
      (footprint "RESC2012X65N")
      (description "Resistor")
      (fields (field (name "MANUFACTURER_PART_NUMBER") "CPF0805B102RE1"))
      (libsource (lib "") (part "CPF0805B102RE1_3"))
    )
    (comp (ref "R21")
      (value "0805 100")
      (footprint "RESC2012X65N")
      (description "Resistor")
      (fields (field (name "MANUFACTURER_PART_NUMBER") "CPF0805B102RE1"))
      (libsource (lib "") (part "CPF0805B102RE1_1"))
    )
    (comp (ref "R22")
      (value "0805 1k")
      (footprint "RESC2012X65N")
      (description "Resistor")
      (fields (field (name "MANUFACTURER_PART_NUMBER") "CPF0805B102RE1"))
      (libsource (lib "") (part "CPF0805B102RE1_3"))
    )
    (comp (ref "R23")
      (value "0805 22k")
      (footprint "RESC2012X65N")
      (description "Resistor")
      (fields (field (name "MANUFACTURER_PART_NUMBER") "CPF0805B102RE1"))
      (libsource (lib "") (part "CPF0805B102RE1_3"))
    )
    (comp (ref "R24")
      (value "0805 22k")
      (footprint "RESC2012X65N")
      (description "Resistor")
      (fields (field (name "MANUFACTURER_PART_NUMBER") "CPF0805B102RE1"))
      (libsource (lib "") (part "CPF0805B102RE1_3"))
    )
    (comp (ref "R25")
      (value "0805 24k")
      (footprint "RESC2012X65N")
      (description "Resistor")
      (fields (field (name "MANUFACTURER_PART_NUMBER") "CPF0805B102RE1"))
      (libsource (lib "*") (part "CPF0805B102RE1"))
    )
    (comp (ref "R26")
      (value "0805 100k")
      (footprint "RESC2012X65N")
      (description "Resistor")
      (fields (field (name "MANUFACTURER_PART_NUMBER") "CPF0805B102RE1"))
      (libsource (lib "") (part "CPF0805B102RE1_3"))
    )
    (comp (ref "R27")
      (value "WSLP08057L000FEA18")
      (footprint "RESC2013X58N")
      (description "Resistor")
      (fields (field (name "MOUSER PART NUMBER") "71-WSLP08057L000FEA1"))
      (libsource (lib "*") (part "WSLP08057L000FEA18"))
    )
    (comp (ref "R28")
      (value "WSLP08057L000FEA18")
      (footprint "RESC2013X58N")
      (description "Resistor")
      (fields (field (name "MOUSER PART NUMBER") "71-WSLP08057L000FEA1"))
      (libsource (lib "*") (part "WSLP08057L000FEA18"))
    )
    (comp (ref "R29")
      (value "WSLP08057L000FEA18")
      (footprint "RESC2013X58N")
      (description "Resistor")
      (fields (field (name "MOUSER PART NUMBER") "71-WSLP08057L000FEA1"))
      (libsource (lib "*") (part "WSLP08057L000FEA18"))
    )
    (comp (ref "R30")
      (value "Jumper")
      (footprint "Solder Jumper 5A")
      (description "Resistor")
      (fields (field (name "MANUFACTURER_PART_NUMBER") "CPF0805B102RE1"))
      (libsource (lib "") (part "CPF0805B102RE1_2"))
    )
    (comp (ref "R31")
      (value "Jumper")
      (footprint "Solder Jumper 9A")
      (description "Resistor")
      (fields (field (name "MANUFACTURER_PART_NUMBER") "CPF0805B102RE1"))
      (libsource (lib "*") (part "CPF0805B102RE1"))
    )
    (comp (ref "R32")
      (value "Jumper")
      (footprint "Solder Jumper 5A")
      (description "Resistor")
      (fields (field (name "MANUFACTURER_PART_NUMBER") "CPF0805B102RE1"))
      (libsource (lib "") (part "CPF0805B102RE1_1"))
    )
    (comp (ref "R33")
      (value "Jumper")
      (footprint "Solder Jumper 5A")
      (description "Resistor")
      (fields (field (name "MANUFACTURER_PART_NUMBER") "CPF0805B102RE1"))
      (libsource (lib "") (part "CPF0805B102RE1_1"))
    )
    (comp (ref "R34")
      (value "Jumper")
      (footprint "Solder Jumper 5A")
      (description "Resistor")
      (fields (field (name "MANUFACTURER_PART_NUMBER") "CPF0805B102RE1"))
      (libsource (lib "") (part "CPF0805B102RE1_2"))
    )
    (comp (ref "R35")
      (value "Jumper")
      (footprint "Solder Jumper 5A")
      (description "Resistor")
      (fields (field (name "MANUFACTURER_PART_NUMBER") "CPF0805B102RE1"))
      (libsource (lib "") (part "CPF0805B102RE1_2"))
    )
    (comp (ref "R36")
      (value "Jumper")
      (footprint "Solder Jumper 9A")
      (description "Resistor")
      (fields (field (name "MANUFACTURER_PART_NUMBER") "CPF0805B102RE1"))
      (libsource (lib "") (part "CPF0805B102RE1_2"))
    )
    (comp (ref "R37")
      (value "0805 390k")
      (footprint "RESC2012X65N")
      (description "Resistor")
      (fields (field (name "MANUFACTURER_PART_NUMBER") "CPF0805B102RE1"))
      (libsource (lib "") (part "CPF0805B102RE1_1"))
    )
    (comp (ref "R38")
      (value "0805 27k")
      (footprint "RESC2012X65N")
      (description "Resistor")
      (fields (field (name "MANUFACTURER_PART_NUMBER") "CPF0805B102RE1"))
      (libsource (lib "") (part "CPF0805B102RE1_1"))
    )
    (comp (ref "R39")
      (value "0805 160")
      (footprint "RESC2012X65N")
      (description "Resistor low tolerance")
      (fields (field (name "MANUFACTURER_PART_NUMBER") "CPF0805B102RE1"))
      (libsource (lib "") (part "CPF0805B102RE1_1"))
    )
    (comp (ref "R40")
      (value "0805 100")
      (footprint "RESC2012X65N")
      (description "Resistor low tolerance")
      (fields (field (name "MANUFACTURER_PART_NUMBER") "CPF0805B102RE1"))
      (libsource (lib "") (part "CPF0805B102RE1_2"))
    )
    (comp (ref "R41")
      (value "0805 260")
      (footprint "RESC2012X65N")
      (description "Resistor low tolerance")
      (fields (field (name "MANUFACTURER_PART_NUMBER") "CPF0805B102RE1"))
      (libsource (lib "") (part "CPF0805B102RE1_1"))
    )
    (comp (ref "R42")
      (value "0805 100")
      (footprint "RESC2012X65N")
      (description "Resistor low tolerance")
      (fields (field (name "MANUFACTURER_PART_NUMBER") "CPF0805B102RE1"))
      (libsource (lib "") (part "CPF0805B102RE1_1"))
    )
    (comp (ref "R43")
      (value "0805 27k")
      (footprint "RESC2012X65N")
      (description "Resistor")
      (fields (field (name "MANUFACTURER_PART_NUMBER") "CPF0805B102RE1"))
      (libsource (lib "") (part "CPF0805B102RE1_1"))
    )
    (comp (ref "R44")
      (value "0805 12k")
      (footprint "RESC2012X65N")
      (description "Resistor")
      (fields (field (name "MANUFACTURER_PART_NUMBER") "CPF0805B102RE1"))
      (libsource (lib "") (part "CPF0805B102RE1_1"))
    )
    (comp (ref "R45")
      (value "0805 22k")
      (footprint "RESC2012X65N")
      (description "Resistor")
      (fields (field (name "MANUFACTURER_PART_NUMBER") "CPF0805B102RE1"))
      (libsource (lib "") (part "CPF0805B102RE1_1"))
    )
    (comp (ref "R46")
      (value "0805 24k")
      (footprint "RESC2012X65N")
      (description "Resistor")
      (fields (field (name "MANUFACTURER_PART_NUMBER") "CPF0805B102RE1"))
      (libsource (lib "*") (part "CPF0805B102RE1"))
    )
    (comp (ref "R47")
      (value "0805 240k")
      (footprint "RESC2012X65N")
      (description "Resistor")
      (fields (field (name "MANUFACTURER_PART_NUMBER") "CPF0805B102RE1"))
      (libsource (lib "") (part "CPF0805B102RE1_1"))
    )
    (comp (ref "R48")
      (value "0805 100k")
      (footprint "RESC2012X65N")
      (description "Resistor")
      (fields (field (name "MANUFACTURER_PART_NUMBER") "CPF0805B102RE1"))
      (libsource (lib "") (part "CPF0805B102RE1_1"))
    )
    (comp (ref "S1")
      (value "5x5mm Button")
      (footprint "430182070816")
      (description "Switch")
      (fields
        (field (name "MANUFACTURER_PART_NUMBER") "430182050816")
        (field (name "MOUSER PART NUMBER") "710-430182050816")
      )
      (libsource (lib "*") (part "430182050816"))
    )
    (comp (ref "S2")
      (value "5x5mm Button")
      (footprint "430182070816")
      (description "Switch")
      (fields
        (field (name "MANUFACTURER_PART_NUMBER") "430182050816")
        (field (name "MOUSER PART NUMBER") "710-430182050816")
      )
      (libsource (lib "*") (part "430182050816"))
    )
  )
  (nets
    (net (code "1") (name "/ALERT") (class "Default")
      (node (ref "IC1") (pin "8") (pinfunction "IO15_8") (pintype "passive"))
      (node (ref "IC6") (pin "19") (pinfunction "ALERT_19") (pintype "passive"))
      (node (ref "R14") (pin "2") (pinfunction "2_2") (pintype "passive"))
    )
    (net (code "2") (name "/CAL") (class "Default")
      (node (ref "IC1") (pin "28") (pinfunction "IO35_28") (pintype "passive"))
      (node (ref "IC5") (pin "31") (pinfunction "CAL_31") (pintype "input"))
    )
    (net (code "3") (name "/CC1") (class "Default")
      (node (ref "IC6") (pin "1") (pinfunction "CC1DB_1") (pintype "passive"))
      (node (ref "IC6") (pin "2") (pinfunction "CC1_2") (pintype "passive"))
      (node (ref "J2") (pin "A5") (pinfunction "CC1_A5") (pintype "bidirectional"))
    )
    (net (code "4") (name "/CC2") (class "Default")
      (node (ref "IC6") (pin "4") (pinfunction "CC2_4") (pintype "passive"))
      (node (ref "IC6") (pin "5") (pinfunction "CC2DB_5") (pintype "passive"))
      (node (ref "J2") (pin "B5") (pinfunction "CC2_B5") (pintype "bidirectional"))
    )
    (net (code "5") (name "/CHARGE") (class "Default")
      (node (ref "IC1") (pin "11") (pinfunction "IO18_11") (pintype "passive"))
      (node (ref "IC2") (pin "6") (pinfunction "~{EN}_6") (pintype "passive"))
      (node (ref "R45") (pin "1") (pinfunction "1_1") (pintype "passive"))
    )
    (net (code "6") (name "/DN") (class "Default")
      (node (ref "IC1") (pin "13") (pinfunction "IO19_13") (pintype "passive"))
      (node (ref "J2") (pin "A7") (pinfunction "DN1_A7") (pintype "bidirectional"))
      (node (ref "J2") (pin "B7") (pinfunction "DN2_B7") (pintype "bidirectional"))
    )
    (net (code "7") (name "/DP") (class "Default")
      (node (ref "IC1") (pin "14") (pinfunction "IO20_14") (pintype "passive"))
      (node (ref "J2") (pin "A6") (pinfunction "DP1_A6") (pintype "bidirectional"))
      (node (ref "J2") (pin "B6") (pinfunction "DP2_B6") (pintype "bidirectional"))
    )
    (net (code "8") (name "/EN") (class "Default")
      (node (ref "C10") (pin "1") (pinfunction "1_1") (pintype "passive"))
      (node (ref "IC1") (pin "3") (pinfunction "EN_3") (pintype "passive"))
      (node (ref "R7") (pin "2") (pinfunction "2_2") (pintype "passive"))
      (node (ref "S2") (pin "2") (pinfunction "2_2") (pintype "passive"))
      (node (ref "S2") (pin "4") (pinfunction "4_4") (pintype "passive"))
    )
    (net (code "9") (name "/ENABLE") (class "Default")
      (node (ref "IC1") (pin "29") (pinfunction "IO36_29") (pintype "passive"))
      (node (ref "IC5") (pin "30") (pinfunction "ENABLE_30") (pintype "input"))
    )
    (net (code "10") (name "/GHA") (class "Default")
      (node (ref "IC5") (pin "6") (pinfunction "GHA_6") (pintype "output"))
      (node (ref "Q5") (pin "1") (pinfunction "G_1") (pintype "passive"))
    )
    (net (code "11") (name "/GHB") (class "Default")
      (node (ref "IC5") (pin "15") (pinfunction "GHB_15") (pintype "output"))
      (node (ref "Q6") (pin "1") (pinfunction "G_1") (pintype "passive"))
    )
    (net (code "12") (name "/GHC") (class "Default")
      (node (ref "IC5") (pin "16") (pinfunction "GHC_16") (pintype "output"))
      (node (ref "Q7") (pin "1") (pinfunction "G_1") (pintype "passive"))
    )
    (net (code "13") (name "/GLA") (class "Default")
      (node (ref "IC5") (pin "8") (pinfunction "GLA_8") (pintype "output"))
      (node (ref "Q8") (pin "1") (pinfunction "G_1") (pintype "passive"))
    )
    (net (code "14") (name "/GLB") (class "Default")
      (node (ref "IC5") (pin "13") (pinfunction "GLB_13") (pintype "output"))
      (node (ref "Q9") (pin "1") (pinfunction "G_1") (pintype "passive"))
    )
    (net (code "15") (name "/GLC") (class "Default")
      (node (ref "IC5") (pin "18") (pinfunction "GLC_18") (pintype "output"))
      (node (ref "Q10") (pin "1") (pinfunction "G_1") (pintype "passive"))
    )
    (net (code "16") (name "/INHA") (class "Default")
      (node (ref "IC1") (pin "17") (pinfunction "IO9_17") (pintype "passive"))
      (node (ref "IC5") (pin "34") (pinfunction "INHA_34") (pintype "input"))
    )
    (net (code "17") (name "/INHB") (class "Default")
      (node (ref "IC1") (pin "19") (pinfunction "IO11_19") (pintype "passive"))
      (node (ref "IC5") (pin "36") (pinfunction "INHB_36") (pintype "input"))
    )
    (net (code "18") (name "/INHC") (class "Default")
      (node (ref "IC1") (pin "21") (pinfunction "IO13_21") (pintype "passive"))
      (node (ref "IC5") (pin "38") (pinfunction "INHC_38") (pintype "input"))
    )
    (net (code "19") (name "/INLA") (class "Default")
      (node (ref "IC1") (pin "18") (pinfunction "IO10_18") (pintype "passive"))
      (node (ref "IC5") (pin "35") (pinfunction "INLA_35") (pintype "input"))
    )
    (net (code "20") (name "/INLB") (class "Default")
      (node (ref "IC1") (pin "20") (pinfunction "IO12_20") (pintype "passive"))
      (node (ref "IC5") (pin "37") (pinfunction "INLB_37") (pintype "input"))
    )
    (net (code "21") (name "/INLC") (class "Default")
      (node (ref "IC1") (pin "23") (pinfunction "IO21_23") (pintype "passive"))
      (node (ref "IC5") (pin "39") (pinfunction "INLC_39") (pintype "input"))
    )
    (net (code "22") (name "/IO0") (class "Default")
      (node (ref "C6") (pin "2") (pinfunction "2_2") (pintype "passive"))
      (node (ref "IC1") (pin "27") (pinfunction "IO0_27") (pintype "passive"))
      (node (ref "R2") (pin "2") (pinfunction "2_2") (pintype "passive"))
      (node (ref "S1") (pin "1") (pinfunction "1_1") (pintype "passive"))
      (node (ref "S1") (pin "3") (pinfunction "3_3") (pintype "passive"))
    )
    (net (code "23") (name "/LEDC") (class "Default")
      (node (ref "IC1") (pin "5") (pinfunction "IO5_5") (pintype "passive"))
      (node (ref "IC8") (pin "5") (pinfunction "CIN_5") (pintype "passive"))
    )
    (net (code "24") (name "/LEDD") (class "Default")
      (node (ref "IC1") (pin "4") (pinfunction "IO4_4") (pintype "passive"))
      (node (ref "IC8") (pin "4") (pinfunction "DIN_4") (pintype "passive"))
    )
    (net (code "25") (name "/MISO_DRV") (class "Default")
      (node (ref "IC1") (pin "33") (pinfunction "IO40_33") (pintype "passive"))
      (node (ref "IC5") (pin "26") (pinfunction "SDO_26") (pintype "passive"))
    )
    (net (code "26") (name "/MOSI_DRV") (class "Default")
      (node (ref "IC1") (pin "32") (pinfunction "IO39_32") (pintype "passive"))
      (node (ref "IC5") (pin "27") (pinfunction "SDI_27") (pintype "input"))
    )
    (net (code "27") (name "/NFAULT") (class "Default")
      (node (ref "IC1") (pin "6") (pinfunction "IO6_6") (pintype "passive"))
      (node (ref "IC5") (pin "25") (pinfunction "NFAULT_25") (pintype "passive"))
      (node (ref "R25") (pin "2") (pinfunction "2_2") (pintype "passive"))
    )
    (net (code "28") (name "/PWM_Servo") (class "Default")
      (node (ref "IC1") (pin "25") (pinfunction "IO48_25") (pintype "passive"))
    )
    (net (code "29") (name "/RESET") (class "Default")
      (node (ref "IC1") (pin "15") (pinfunction "IO3_15") (pintype "passive"))
      (node (ref "IC6") (pin "6") (pinfunction "RESET_6") (pintype "passive"))
      (node (ref "R26") (pin "2") (pinfunction "2_2") (pintype "passive"))
    )
    (net (code "30") (name "/RXD") (class "Default")
      (node (ref "IC1") (pin "36") (pinfunction "RXD0_36") (pintype "passive"))
    )
    (net (code "31") (name "/SCL") (class "Default")
      (node (ref "IC1") (pin "10") (pinfunction "IO17_10") (pintype "passive"))
      (node (ref "IC6") (pin "7") (pinfunction "SCL_7") (pintype "passive"))
      (node (ref "R9") (pin "2") (pinfunction "2_2") (pintype "passive"))
    )
    (net (code "32") (name "/SCLK") (class "Default")
      (node (ref "IC1") (pin "31") (pinfunction "IO38_31") (pintype "passive"))
      (node (ref "IC5") (pin "28") (pinfunction "SCLK_28") (pintype "input"))
    )
    (net (code "33") (name "/SDA") (class "Default")
      (node (ref "IC1") (pin "9") (pinfunction "IO16_9") (pintype "passive"))
      (node (ref "IC6") (pin "8") (pinfunction "SDA_8") (pintype "passive"))
      (node (ref "R11") (pin "2") (pinfunction "2_2") (pintype "passive"))
    )
    (net (code "34") (name "/SHA") (class "Default")
      (node (ref "IC5") (pin "7") (pinfunction "SHA_7") (pintype "input"))
      (node (ref "Q5") (pin "3") (pinfunction "S_3") (pintype "passive"))
      (node (ref "Q8") (pin "2") (pinfunction "D_2") (pintype "passive"))
    )
    (net (code "35") (name "/SHB") (class "Default")
      (node (ref "IC5") (pin "14") (pinfunction "SHB_14") (pintype "input"))
      (node (ref "Q6") (pin "3") (pinfunction "S_3") (pintype "passive"))
      (node (ref "Q9") (pin "2") (pinfunction "D_2") (pintype "passive"))
    )
    (net (code "36") (name "/SHC") (class "Default")
      (node (ref "IC5") (pin "17") (pinfunction "SHC_17") (pintype "input"))
      (node (ref "Q10") (pin "2") (pinfunction "D_2") (pintype "passive"))
      (node (ref "Q7") (pin "3") (pinfunction "S_3") (pintype "passive"))
    )
    (net (code "37") (name "/SOA") (class "Default")
      (node (ref "IC1") (pin "34") (pinfunction "IO41_34") (pintype "passive"))
      (node (ref "IC5") (pin "23") (pinfunction "SOA_23") (pintype "output"))
    )
    (net (code "38") (name "/SOB") (class "Default")
      (node (ref "IC1") (pin "35") (pinfunction "IO42_35") (pintype "passive"))
      (node (ref "IC5") (pin "22") (pinfunction "SOB_22") (pintype "output"))
    )
    (net (code "39") (name "/SOC") (class "Default")
      (node (ref "IC1") (pin "38") (pinfunction "IO2_38") (pintype "passive"))
      (node (ref "IC5") (pin "21") (pinfunction "SOC_21") (pintype "output"))
    )
    (net (code "40") (name "/SPA") (class "Default")
      (node (ref "IC5") (pin "9") (pinfunction "SPA_9") (pintype "input"))
      (node (ref "Q8") (pin "3") (pinfunction "S_3") (pintype "passive"))
      (node (ref "R27") (pin "2") (pinfunction "2_2") (pintype "passive"))
    )
    (net (code "41") (name "/SPB") (class "Default")
      (node (ref "IC5") (pin "12") (pinfunction "SPB_12") (pintype "input"))
      (node (ref "Q9") (pin "3") (pinfunction "S_3") (pintype "passive"))
      (node (ref "R28") (pin "2") (pinfunction "2_2") (pintype "passive"))
    )
    (net (code "42") (name "/SPC") (class "Default")
      (node (ref "IC5") (pin "19") (pinfunction "SPC_19") (pintype "input"))
      (node (ref "Q10") (pin "3") (pinfunction "S_3") (pintype "passive"))
      (node (ref "R29") (pin "2") (pinfunction "2_2") (pintype "passive"))
    )
    (net (code "43") (name "/SS") (class "Default")
      (node (ref "IC1") (pin "30") (pinfunction "IO37_30") (pintype "passive"))
      (node (ref "IC5") (pin "29") (pinfunction "NSCS_29") (pintype "input"))
      (node (ref "R46") (pin "2") (pinfunction "2_2") (pintype "passive"))
    )
    (net (code "44") (name "/ST") (class "Default")
      (node (ref "IC1") (pin "7") (pinfunction "IO7_7") (pintype "passive"))
      (node (ref "IC4") (pin "9") (pinfunction "ST_9") (pintype "passive"))
      (node (ref "R15") (pin "1") (pinfunction "1_1") (pintype "passive"))
    )
    (net (code "45") (name "/TXD") (class "Default")
      (node (ref "IC1") (pin "37") (pinfunction "TXD0_37") (pintype "passive"))
    )
    (net (code "46") (name "/VBATADC") (class "Default")
      (node (ref "C41") (pin "2") (pinfunction "2_2") (pintype "passive"))
      (node (ref "IC1") (pin "12") (pinfunction "IO8_12") (pintype "passive"))
      (node (ref "R43") (pin "1") (pinfunction "1_1") (pintype "passive"))
      (node (ref "R44") (pin "2") (pinfunction "2_2") (pintype "passive"))
    )
    (net (code "47") (name "/VBUSADC") (class "Default")
      (node (ref "C36") (pin "2") (pinfunction "2_2") (pintype "passive"))
      (node (ref "IC1") (pin "22") (pinfunction "IO14_22") (pintype "passive"))
      (node (ref "R37") (pin "1") (pinfunction "1_1") (pintype "passive"))
      (node (ref "R38") (pin "2") (pinfunction "2_2") (pintype "passive"))
    )
    (net (code "48") (name "3V3") (class "Default")
      (node (ref "C1") (pin "1") (pinfunction "1_1") (pintype "passive"))
      (node (ref "C2") (pin "1") (pinfunction "1_1") (pintype "passive"))
      (node (ref "C3") (pin "2") (pinfunction "2_2") (pintype "passive"))
      (node (ref "C35") (pin "2") (pinfunction "2_2") (pintype "passive"))
      (node (ref "C4") (pin "2") (pinfunction "2_2") (pintype "passive"))
      (node (ref "IC1") (pin "2") (pinfunction "3V3_2") (pintype "passive"))
      (node (ref "IC5") (pin "24") (pinfunction "VREF_24") (pintype "power_in"))
      (node (ref "IC5") (pin "33") (pinfunction "DVDD_33") (pintype "power_in"))
      (node (ref "IC8") (pin "1") (pinfunction "VDD_1") (pintype "passive"))
      (node (ref "L1") (pin "1") (pinfunction "1_1") (pintype "passive"))
      (node (ref "R1") (pin "2") (pinfunction "2_2") (pintype "passive"))
      (node (ref "R11") (pin "1") (pinfunction "1_1") (pintype "passive"))
      (node (ref "R14") (pin "1") (pinfunction "1_1") (pintype "passive"))
      (node (ref "R15") (pin "2") (pinfunction "2_2") (pintype "passive"))
      (node (ref "R2") (pin "1") (pinfunction "1_1") (pintype "passive"))
      (node (ref "R25") (pin "1") (pinfunction "1_1") (pintype "passive"))
      (node (ref "R45") (pin "2") (pinfunction "2_2") (pintype "passive"))
      (node (ref "R46") (pin "1") (pinfunction "1_1") (pintype "passive"))
      (node (ref "R7") (pin "1") (pinfunction "1_1") (pintype "passive"))
      (node (ref "R9") (pin "1") (pinfunction "1_1") (pintype "passive"))
    )
    (net (code "49") (name "GND") (class "Default")
      (node (ref "C1") (pin "2") (pinfunction "2_2") (pintype "passive"))
      (node (ref "C10") (pin "2") (pinfunction "2_2") (pintype "passive"))
      (node (ref "C12") (pin "1") (pinfunction "1_1") (pintype "passive"))
      (node (ref "C13") (pin "1") (pinfunction "1_1") (pintype "passive"))
      (node (ref "C15") (pin "1") (pinfunction "1_1") (pintype "passive"))
      (node (ref "C16") (pin "1") (pinfunction "1_1") (pintype "passive"))
      (node (ref "C18") (pin "2") (pinfunction "2_2") (pintype "passive"))
      (node (ref "C2") (pin "2") (pinfunction "2_2") (pintype "passive"))
      (node (ref "C20") (pin "2") (pinfunction "2_2") (pintype "passive"))
      (node (ref "C21") (pin "2") (pinfunction "2_2") (pintype "passive"))
      (node (ref "C22") (pin "1") (pinfunction "1_1") (pintype "passive"))
      (node (ref "C23") (pin "2") (pinfunction "2_2") (pintype "passive"))
      (node (ref "C24") (pin "2") (pinfunction "2_2") (pintype "passive"))
      (node (ref "C25") (pin "2") (pinfunction "2_2") (pintype "passive"))
      (node (ref "C26") (pin "2") (pinfunction "2_2") (pintype "passive"))
      (node (ref "C27") (pin "2") (pinfunction "2_2") (pintype "passive"))
      (node (ref "C28") (pin "2") (pinfunction "2_2") (pintype "passive"))
      (node (ref "C29") (pin "1") (pinfunction "1_1") (pintype "passive"))
      (node (ref "C3") (pin "1") (pinfunction "1_1") (pintype "passive"))
      (node (ref "C30") (pin "1") (pinfunction "1_1") (pintype "passive"))
      (node (ref "C33") (pin "1") (pinfunction "1_1") (pintype "passive"))
      (node (ref "C34") (pin "1") (pinfunction "1_1") (pintype "passive"))
      (node (ref "C35") (pin "1") (pinfunction "1_1") (pintype "passive"))
      (node (ref "C36") (pin "1") (pinfunction "1_1") (pintype "passive"))
      (node (ref "C4") (pin "1") (pinfunction "1_1") (pintype "passive"))
      (node (ref "C41") (pin "1") (pinfunction "1_1") (pintype "passive"))
      (node (ref "C6") (pin "1") (pinfunction "1_1") (pintype "passive"))
      (node (ref "C7") (pin "2") (pinfunction "2_2") (pintype "passive"))
      (node (ref "C8") (pin "1") (pinfunction "1_1") (pintype "passive"))
      (node (ref "C9") (pin "1") (pinfunction "1_1") (pintype "passive"))
      (node (ref "D2") (pin "2") (pinfunction "A_2") (pintype "passive"))
      (node (ref "D3") (pin "2") (pinfunction "A_2") (pintype "passive"))
      (node (ref "IC1") (pin "1") (pinfunction "GND_1_1") (pintype "passive"))
      (node (ref "IC1") (pin "40") (pinfunction "GND_2_40") (pintype "passive"))
      (node (ref "IC1") (pin "41") (pinfunction "GND_3_41") (pintype "passive"))
      (node (ref "IC1") (pin "42") (pinfunction "GND_4_42") (pintype "passive"))
      (node (ref "IC1") (pin "43") (pinfunction "GND_5_43") (pintype "passive"))
      (node (ref "IC1") (pin "44") (pinfunction "GND_6_44") (pintype "passive"))
      (node (ref "IC1") (pin "45") (pinfunction "GND_7_45") (pintype "passive"))
      (node (ref "IC1") (pin "46") (pinfunction "GND_8_46") (pintype "passive"))
      (node (ref "IC1") (pin "47") (pinfunction "GND_9_47") (pintype "passive"))
      (node (ref "IC1") (pin "48") (pinfunction "GND_10_48") (pintype "passive"))
      (node (ref "IC1") (pin "49") (pinfunction "GND_11_49") (pintype "passive"))
      (node (ref "IC2") (pin "16") (pinfunction "PGND_16") (pintype "passive"))
      (node (ref "IC2") (pin "8") (pinfunction "AGND_8") (pintype "passive"))
      (node (ref "IC4") (pin "12") (pinfunction "GND_12") (pintype "passive"))
      (node (ref "IC4") (pin "3") (pinfunction "CP2_3") (pintype "passive"))
      (node (ref "IC4") (pin "4") (pinfunction "OV2_4") (pintype "passive"))
      (node (ref "IC4") (pin "5") (pinfunction "OV1_5") (pintype "passive"))
      (node (ref "IC5") (pin "10") (pinfunction "SNA_10") (pintype "input"))
      (node (ref "IC5") (pin "11") (pinfunction "SNB_11") (pintype "input"))
      (node (ref "IC5") (pin "20") (pinfunction "SNC_20") (pintype "input"))
      (node (ref "IC5") (pin "32") (pinfunction "AGND_32") (pintype "power_in"))
      (node (ref "IC5") (pin "40") (pinfunction "PGND_40") (pintype "power_in"))
      (node (ref "IC5") (pin "41") (pinfunction "EP_41") (pintype "power_in"))
      (node (ref "IC6") (pin "10") (pinfunction "GND_10") (pintype "passive"))
      (node (ref "IC6") (pin "12") (pinfunction "ADDR0_12") (pintype "passive"))
      (node (ref "IC6") (pin "13") (pinfunction "ADDR1_13") (pintype "passive"))
      (node (ref "IC6") (pin "22") (pinfunction "VSYS_22") (pintype "passive"))
      (node (ref "IC6") (pin "25") (pinfunction "EP_25") (pintype "passive"))
      (node (ref "IC8") (pin "6") (pinfunction "GND_6") (pintype "passive"))
      (node (ref "J2") (pin "A1_B12") (pinfunction "GND_A_A1_B12") (pintype "power_in"))
      (node (ref "J2") (pin "B1_A12") (pinfunction "GND_B_B1_A12") (pintype "power_in"))
      (node (ref "J2") (pin "SH1") (pinfunction "SHIELD_SH1") (pintype "passive"))
      (node (ref "J2") (pin "SH2") (pinfunction "SHIELD_SH2") (pintype "passive"))
      (node (ref "J2") (pin "SH3") (pinfunction "SHIELD_SH3") (pintype "passive"))
      (node (ref "J2") (pin "SH4") (pinfunction "SHIELD_SH4") (pintype "passive"))
      (node (ref "PS1") (pin "1") (pinfunction "GND_1") (pintype "power_in"))
      (node (ref "Q2") (pin "3") (pinfunction "S_3") (pintype "passive"))
      (node (ref "R16") (pin "1") (pinfunction "1_1") (pintype "passive"))
      (node (ref "R24") (pin "1") (pinfunction "1_1") (pintype "passive"))
      (node (ref "R26") (pin "1") (pinfunction "1_1") (pintype "passive"))
      (node (ref "R27") (pin "1") (pinfunction "1_1") (pintype "passive"))
      (node (ref "R28") (pin "1") (pinfunction "1_1") (pintype "passive"))
      (node (ref "R29") (pin "1") (pinfunction "1_1") (pintype "passive"))
      (node (ref "R38") (pin "1") (pinfunction "1_1") (pintype "passive"))
      (node (ref "R4") (pin "1") (pinfunction "1_1") (pintype "passive"))
      (node (ref "R44") (pin "1") (pinfunction "1_1") (pintype "passive"))
      (node (ref "R48") (pin "1") (pinfunction "1_1") (pintype "passive"))
      (node (ref "R5") (pin "1") (pinfunction "1_1") (pintype "passive"))
      (node (ref "S1") (pin "2") (pinfunction "2_2") (pintype "passive"))
      (node (ref "S1") (pin "4") (pinfunction "4_4") (pintype "passive"))
      (node (ref "S2") (pin "1") (pinfunction "1_1") (pintype "passive"))
      (node (ref "S2") (pin "3") (pinfunction "3_3") (pintype "passive"))
    )
    (net (code "50") (name "Net-(C19-Pad2)") (class "Default")
      (node (ref "C19") (pin "2") (pinfunction "2_2") (pintype "passive"))
      (node (ref "R21") (pin "1") (pinfunction "1_1") (pintype "passive"))
    )
    (net (code "51") (name "Net-(D1-K)") (class "Default")
      (node (ref "C25") (pin "1") (pinfunction "1_1") (pintype "passive"))
      (node (ref "D1") (pin "1") (pinfunction "K_1") (pintype "passive"))
      (node (ref "R18") (pin "1") (pinfunction "1_1") (pintype "passive"))
      (node (ref "R22") (pin "2") (pinfunction "2_2") (pintype "passive"))
    )
    (net (code "52") (name "Net-(D3-K)") (class "Default")
      (node (ref "C19") (pin "1") (pinfunction "1_1") (pintype "passive"))
      (node (ref "D3") (pin "1") (pinfunction "K_1") (pintype "passive"))
      (node (ref "Q4") (pin "2") (pinfunction "D_2") (pintype "passive"))
      (node (ref "R20") (pin "2") (pinfunction "2_2") (pintype "passive"))
      (node (ref "R33") (pin "2") (pinfunction "2_2") (pintype "passive"))
    )
    (net (code "53") (name "Net-(IC2-BST)") (class "Default")
      (node (ref "C11") (pin "1") (pinfunction "1_1") (pintype "passive"))
      (node (ref "IC2") (pin "15") (pinfunction "BST_15") (pintype "passive"))
    )
    (net (code "54") (name "Net-(IC2-CSP)") (class "Default")
      (node (ref "IC2") (pin "10") (pinfunction "CSP_10") (pintype "passive"))
      (node (ref "L2") (pin "1") (pinfunction "1_1") (pintype "passive"))
      (node (ref "R6") (pin "1") (pinfunction "1_1") (pintype "passive"))
    )
    (net (code "55") (name "Net-(IC2-NTC)") (class "Default")
      (node (ref "IC2") (pin "13") (pinfunction "NTC_13") (pintype "passive"))
      (node (ref "R3") (pin "1") (pinfunction "1_1") (pintype "passive"))
      (node (ref "R4") (pin "2") (pinfunction "2_2") (pintype "passive"))
    )
    (net (code "56") (name "Net-(IC2-SW)") (class "Default")
      (node (ref "C11") (pin "2") (pinfunction "2_2") (pintype "passive"))
      (node (ref "IC2") (pin "1") (pinfunction "SW_1") (pintype "passive"))
      (node (ref "L2") (pin "2") (pinfunction "2_2") (pintype "passive"))
    )
    (net (code "57") (name "Net-(IC2-TMR)") (class "Default")
      (node (ref "C7") (pin "1") (pinfunction "1_1") (pintype "passive"))
      (node (ref "IC2") (pin "14") (pinfunction "TMR_14") (pintype "passive"))
    )
    (net (code "58") (name "Net-(IC2-VCC)") (class "Default")
      (node (ref "C9") (pin "2") (pinfunction "2_2") (pintype "passive"))
      (node (ref "IC2") (pin "3") (pinfunction "VCC_3") (pintype "passive"))
      (node (ref "R3") (pin "2") (pinfunction "2_2") (pintype "passive"))
    )
    (net (code "59") (name "Net-(IC2-VIN)") (class "Default")
      (node (ref "C12") (pin "2") (pinfunction "2_2") (pintype "passive"))
      (node (ref "C13") (pin "2") (pinfunction "2_2") (pintype "passive"))
      (node (ref "IC2") (pin "2") (pinfunction "VIN_2") (pintype "passive"))
      (node (ref "LED1") (pin "2") (pinfunction "A_2") (pintype "passive"))
      (node (ref "R30") (pin "2") (pinfunction "2_2") (pintype "passive"))
    )
    (net (code "60") (name "Net-(IC2-~{CHGOK})") (class "Default")
      (node (ref "IC2") (pin "11") (pinfunction "~{CHGOK}_11") (pintype "passive"))
      (node (ref "R8") (pin "1") (pinfunction "1_1") (pintype "passive"))
    )
    (net (code "61") (name "Net-(IC3-CO)") (class "Default")
      (node (ref "IC3") (pin "3") (pinfunction "CO_3") (pintype "passive"))
      (node (ref "Q2") (pin "1") (pinfunction "G_1") (pintype "passive"))
    )
    (net (code "62") (name "Net-(IC3-CTL)") (class "Default")
      (node (ref "IC3") (pin "1") (pinfunction "CTL_1") (pintype "passive"))
      (node (ref "R12") (pin "1") (pinfunction "1_1") (pintype "passive"))
    )
    (net (code "63") (name "Net-(IC3-DO)") (class "Default")
      (node (ref "IC3") (pin "4") (pinfunction "DO_4") (pintype "passive"))
      (node (ref "Q1") (pin "1") (pinfunction "G_1") (pintype "passive"))
    )
    (net (code "64") (name "Net-(IC3-EP)") (class "Default")
      (node (ref "C14") (pin "2") (pinfunction "2_2") (pintype "passive"))
      (node (ref "IC3") (pin "8") (pinfunction "VDD_8") (pintype "passive"))
      (node (ref "IC3") (pin "9") (pinfunction "EP_9") (pintype "passive"))
      (node (ref "R10") (pin "1") (pinfunction "1_1") (pintype "passive"))
    )
    (net (code "65") (name "Net-(IC3-VC)") (class "Default")
      (node (ref "C17") (pin "2") (pinfunction "2_2") (pintype "passive"))
      (node (ref "IC3") (pin "7") (pinfunction "VC_7") (pintype "passive"))
      (node (ref "R13") (pin "1") (pinfunction "1_1") (pintype "passive"))
    )
    (net (code "66") (name "Net-(IC3-VINI)") (class "Default")
      (node (ref "IC3") (pin "5") (pinfunction "VINI_5") (pintype "passive"))
      (node (ref "Q1") (pin "3") (pinfunction "S_3") (pintype "passive"))
      (node (ref "R17") (pin "1") (pinfunction "1_1") (pintype "passive"))
    )
    (net (code "67") (name "Net-(IC3-VM)") (class "Default")
      (node (ref "IC3") (pin "2") (pinfunction "VM_2") (pintype "passive"))
      (node (ref "R16") (pin "2") (pinfunction "2_2") (pintype "passive"))
    )
    (net (code "68") (name "Net-(IC4-ILIM)") (class "Default")
      (node (ref "IC4") (pin "10") (pinfunction "ILIM_10") (pintype "passive"))
      (node (ref "R24") (pin "2") (pinfunction "2_2") (pintype "passive"))
    )
    (net (code "69") (name "Net-(IC4-IN1)") (class "Default")
      (node (ref "C20") (pin "1") (pinfunction "1_1") (pintype "passive"))
      (node (ref "C21") (pin "1") (pinfunction "1_1") (pintype "passive"))
      (node (ref "IC4") (pin "7") (pinfunction "IN1_7") (pintype "passive"))
      (node (ref "R32") (pin "1") (pinfunction "1_1") (pintype "passive"))
      (node (ref "R47") (pin "2") (pinfunction "2_2") (pintype "passive"))
    )
    (net (code "70") (name "Net-(IC4-IN2)") (class "Default")
      (node (ref "C27") (pin "1") (pinfunction "1_1") (pintype "passive"))
      (node (ref "C28") (pin "1") (pinfunction "1_1") (pintype "passive"))
      (node (ref "IC4") (pin "2") (pinfunction "IN2_2") (pintype "passive"))
      (node (ref "R35") (pin "2") (pinfunction "2_2") (pintype "passive"))
    )
    (net (code "71") (name "Net-(IC4-OUT_1)") (class "Default")
      (node (ref "C23") (pin "1") (pinfunction "1_1") (pintype "passive"))
      (node (ref "C24") (pin "1") (pinfunction "1_1") (pintype "passive"))
      (node (ref "IC4") (pin "1") (pinfunction "OUT_1_1") (pintype "passive"))
      (node (ref "IC4") (pin "8") (pinfunction "OUT_2_8") (pintype "passive"))
      (node (ref "R34") (pin "2") (pinfunction "2_2") (pintype "passive"))
    )
    (net (code "72") (name "Net-(IC4-PR1)") (class "Default")
      (node (ref "IC4") (pin "6") (pinfunction "PR1_6") (pintype "passive"))
      (node (ref "R47") (pin "1") (pinfunction "1_1") (pintype "passive"))
      (node (ref "R48") (pin "2") (pinfunction "2_2") (pintype "passive"))
    )
    (net (code "73") (name "Net-(IC4-SS)") (class "Default")
      (node (ref "C30") (pin "2") (pinfunction "2_2") (pintype "passive"))
      (node (ref "IC4") (pin "11") (pinfunction "SS_11") (pintype "passive"))
    )
    (net (code "74") (name "Net-(IC5-CPH)") (class "Default")
      (node (ref "C31") (pin "1") (pinfunction "1_1") (pintype "passive"))
      (node (ref "IC5") (pin "2") (pinfunction "CPH_2") (pintype "power_in"))
    )
    (net (code "75") (name "Net-(IC5-CPL)") (class "Default")
      (node (ref "C31") (pin "2") (pinfunction "2_2") (pintype "passive"))
      (node (ref "IC5") (pin "1") (pinfunction "CPL_1") (pintype "power_in"))
    )
    (net (code "76") (name "Net-(IC5-VCP)") (class "Default")
      (node (ref "C32") (pin "2") (pinfunction "2_2") (pintype "passive"))
      (node (ref "IC5") (pin "3") (pinfunction "VCP_3") (pintype "power_in"))
    )
    (net (code "77") (name "Net-(IC6-DISCH)") (class "Default")
      (node (ref "IC6") (pin "9") (pinfunction "DISCH_9") (pintype "passive"))
      (node (ref "R20") (pin "1") (pinfunction "1_1") (pintype "passive"))
    )
    (net (code "78") (name "Net-(IC6-VBUS_EN_SNK)") (class "Default")
      (node (ref "IC6") (pin "16") (pinfunction "VBUS_EN_SNK_16") (pintype "passive"))
      (node (ref "R23") (pin "1") (pinfunction "1_1") (pintype "passive"))
    )
    (net (code "79") (name "Net-(IC6-VBUS_VS_DISCH)") (class "Default")
      (node (ref "IC6") (pin "18") (pinfunction "VBUS_VS_DISCH_18") (pintype "passive"))
      (node (ref "R22") (pin "1") (pinfunction "1_1") (pintype "passive"))
    )
    (net (code "80") (name "Net-(IC6-VDD)") (class "Default")
      (node (ref "C22") (pin "2") (pinfunction "2_2") (pintype "passive"))
      (node (ref "IC6") (pin "24") (pinfunction "VDD_24") (pintype "passive"))
      (node (ref "Q3") (pin "3") (pinfunction "S_3") (pintype "passive"))
      (node (ref "Q4") (pin "3") (pinfunction "S_3") (pintype "passive"))
      (node (ref "R19") (pin "2") (pinfunction "2_2") (pintype "passive"))
    )
    (net (code "81") (name "Net-(IC6-VREG_1V2)") (class "Default")
      (node (ref "C29") (pin "2") (pinfunction "2_2") (pintype "passive"))
      (node (ref "IC6") (pin "21") (pinfunction "VREG_1V2_21") (pintype "passive"))
    )
    (net (code "82") (name "Net-(IC6-VREG_2V7)") (class "Default")
      (node (ref "C26") (pin "1") (pinfunction "1_1") (pintype "passive"))
      (node (ref "IC6") (pin "23") (pinfunction "VREG_2V7_23") (pintype "passive"))
    )
    (net (code "83") (name "Net-(IC7-CD)") (class "Default")
      (node (ref "C39") (pin "2") (pinfunction "2_2") (pintype "passive"))
      (node (ref "IC7") (pin "4") (pinfunction "CD_4") (pintype "passive"))
    )
    (net (code "84") (name "Net-(IC7-VC1)") (class "Default")
      (node (ref "C37") (pin "1") (pinfunction "1_1") (pintype "passive"))
      (node (ref "C38") (pin "2") (pinfunction "2_2") (pintype "passive"))
      (node (ref "IC7") (pin "2") (pinfunction "VC1_2") (pintype "passive"))
      (node (ref "R41") (pin "1") (pinfunction "1_1") (pintype "passive"))
    )
    (net (code "85") (name "Net-(IC7-VC1_CB)") (class "Default")
      (node (ref "IC7") (pin "3") (pinfunction "VC1_CB_3") (pintype "passive"))
      (node (ref "R42") (pin "1") (pinfunction "1_1") (pintype "passive"))
    )
    (net (code "86") (name "Net-(IC7-VC2)") (class "Default")
      (node (ref "C37") (pin "2") (pinfunction "2_2") (pintype "passive"))
      (node (ref "IC7") (pin "1") (pinfunction "VC2_1") (pintype "passive"))
      (node (ref "R39") (pin "1") (pinfunction "1_1") (pintype "passive"))
    )
    (net (code "87") (name "Net-(IC7-VDD)") (class "Default")
      (node (ref "C40") (pin "2") (pinfunction "2_2") (pintype "passive"))
      (node (ref "IC7") (pin "7") (pinfunction "VDD_7") (pintype "passive"))
      (node (ref "R40") (pin "2") (pinfunction "2_2") (pintype "passive"))
    )
    (net (code "88") (name "Net-(LED1-K)") (class "Default")
      (node (ref "LED1") (pin "1") (pinfunction "K_1") (pintype "passive"))
      (node (ref "R8") (pin "2") (pinfunction "2_2") (pintype "passive"))
    )
    (net (code "89") (name "Net-(PS1-CB)") (class "Default")
      (node (ref "C5") (pin "1") (pinfunction "1_1") (pintype "passive"))
      (node (ref "PS1") (pin "6") (pinfunction "CB_6") (pintype "power_in"))
    )
    (net (code "90") (name "Net-(PS1-FB)") (class "Default")
      (node (ref "PS1") (pin "4") (pinfunction "FB_4") (pintype "input"))
      (node (ref "R1") (pin "1") (pinfunction "1_1") (pintype "passive"))
      (node (ref "R5") (pin "2") (pinfunction "2_2") (pintype "passive"))
    )
    (net (code "91") (name "Net-(PS1-SW)") (class "Default")
      (node (ref "C5") (pin "2") (pinfunction "2_2") (pintype "passive"))
      (node (ref "L1") (pin "2") (pinfunction "2_2") (pintype "passive"))
      (node (ref "PS1") (pin "2") (pinfunction "SW_2") (pintype "power_in"))
    )
    (net (code "92") (name "Net-(Q1-D)") (class "Default")
      (node (ref "Q1") (pin "2") (pinfunction "D_2") (pintype "passive"))
      (node (ref "Q2") (pin "2") (pinfunction "D_2") (pintype "passive"))
    )
    (net (code "93") (name "Net-(Q3-G)") (class "Default")
      (node (ref "Q3") (pin "1") (pinfunction "G_1") (pintype "passive"))
      (node (ref "Q4") (pin "1") (pinfunction "G_1") (pintype "passive"))
      (node (ref "R19") (pin "1") (pinfunction "1_1") (pintype "passive"))
      (node (ref "R21") (pin "2") (pinfunction "2_2") (pintype "passive"))
      (node (ref "R23") (pin "2") (pinfunction "2_2") (pintype "passive"))
    )
    (net (code "94") (name "VBAT+") (class "Default")
      (node (ref "C15") (pin "2") (pinfunction "2_2") (pintype "passive"))
      (node (ref "C16") (pin "2") (pinfunction "2_2") (pintype "passive"))
      (node (ref "IC2") (pin "9") (pinfunction "BATT_9") (pintype "passive"))
      (node (ref "J1") (pin "1") (pinfunction "1_1") (pintype "passive"))
      (node (ref "J3") (pin "1") (pinfunction "1_1") (pintype "passive"))
      (node (ref "R10") (pin "2") (pinfunction "2_2") (pintype "passive"))
      (node (ref "R12") (pin "2") (pinfunction "2_2") (pintype "passive"))
      (node (ref "R31") (pin "1") (pinfunction "1_1") (pintype "passive"))
      (node (ref "R39") (pin "2") (pinfunction "2_2") (pintype "passive"))
      (node (ref "R40") (pin "1") (pinfunction "1_1") (pintype "passive"))
      (node (ref "R43") (pin "2") (pinfunction "2_2") (pintype "passive"))
      (node (ref "R6") (pin "2") (pinfunction "2_2") (pintype "passive"))
    )
    (net (code "95") (name "VBAT-") (class "Default")
      (node (ref "C14") (pin "1") (pinfunction "1_1") (pintype "passive"))
      (node (ref "C17") (pin "1") (pinfunction "1_1") (pintype "passive"))
      (node (ref "C38") (pin "1") (pinfunction "1_1") (pintype "passive"))
      (node (ref "C39") (pin "1") (pinfunction "1_1") (pintype "passive"))
      (node (ref "C40") (pin "1") (pinfunction "1_1") (pintype "passive"))
      (node (ref "IC3") (pin "6") (pinfunction "VSS_6") (pintype "passive"))
      (node (ref "IC7") (pin "5") (pinfunction "GND_1_5") (pintype "passive"))
      (node (ref "IC7") (pin "6") (pinfunction "~{CB_EN}_6") (pintype "passive"))
      (node (ref "IC7") (pin "9") (pinfunction "GND_2_9") (pintype "passive"))
      (node (ref "J1") (pin "3") (pinfunction "3_3") (pintype "passive"))
      (node (ref "J3") (pin "2") (pinfunction "2_2") (pintype "passive"))
      (node (ref "R17") (pin "2") (pinfunction "2_2") (pintype "passive"))
    )
    (net (code "96") (name "VBATJ") (class "Default")
      (node (ref "R31") (pin "2") (pinfunction "2_2") (pintype "passive"))
      (node (ref "R35") (pin "1") (pinfunction "1_1") (pintype "passive"))
      (node (ref "R36") (pin "1") (pinfunction "1_1") (pintype "passive"))
    )
    (net (code "97") (name "VBATM") (class "Default")
      (node (ref "J1") (pin "2") (pinfunction "2_2") (pintype "passive"))
      (node (ref "R13") (pin "2") (pinfunction "2_2") (pintype "passive"))
      (node (ref "R41") (pin "2") (pinfunction "2_2") (pintype "passive"))
      (node (ref "R42") (pin "2") (pinfunction "2_2") (pintype "passive"))
    )
    (net (code "98") (name "VBUS") (class "Default")
      (node (ref "C18") (pin "1") (pinfunction "1_1") (pintype "passive"))
      (node (ref "D1") (pin "2") (pinfunction "A_2") (pintype "passive"))
      (node (ref "D2") (pin "1") (pinfunction "K_1") (pintype "passive"))
      (node (ref "J2") (pin "A4_B9") (pinfunction "VBUS_A_A4_B9") (pintype "power_in"))
      (node (ref "J2") (pin "B4_A9") (pinfunction "VBUS_B_B4_A9") (pintype "power_in"))
      (node (ref "Q3") (pin "2") (pinfunction "D_2") (pintype "passive"))
      (node (ref "R18") (pin "2") (pinfunction "2_2") (pintype "passive"))
      (node (ref "R37") (pin "2") (pinfunction "2_2") (pintype "passive"))
    )
    (net (code "99") (name "VDRAIN") (class "Default")
      (node (ref "C32") (pin "1") (pinfunction "1_1") (pintype "passive"))
      (node (ref "C33") (pin "2") (pinfunction "2_2") (pintype "passive"))
      (node (ref "C34") (pin "2") (pinfunction "2_2") (pintype "passive"))
      (node (ref "IC5") (pin "4") (pinfunction "VM_4") (pintype "power_in"))
      (node (ref "IC5") (pin "5") (pinfunction "VDRAIN_5") (pintype "input"))
      (node (ref "Q5") (pin "2") (pinfunction "D_2") (pintype "passive"))
      (node (ref "Q6") (pin "2") (pinfunction "D_2") (pintype "passive"))
      (node (ref "Q7") (pin "2") (pinfunction "D_2") (pintype "passive"))
      (node (ref "R36") (pin "2") (pinfunction "2_2") (pintype "passive"))
    )
    (net (code "100") (name "VMCU") (class "Default")
      (node (ref "C8") (pin "2") (pinfunction "2_2") (pintype "passive"))
      (node (ref "PS1") (pin "3") (pinfunction "VIN_3") (pintype "power_in"))
      (node (ref "PS1") (pin "5") (pinfunction "EN_5") (pintype "input"))
      (node (ref "R34") (pin "1") (pinfunction "1_1") (pintype "passive"))
    )
    (net (code "101") (name "VSYS") (class "Default")
      (node (ref "R30") (pin "1") (pinfunction "1_1") (pintype "passive"))
      (node (ref "R32") (pin "2") (pinfunction "2_2") (pintype "passive"))
      (node (ref "R33") (pin "1") (pinfunction "1_1") (pintype "passive"))
    )
    (net (code "102") (name "unconnected-(IC1-IO1-Pad39)") (class "Default")
      (node (ref "IC1") (pin "39") (pinfunction "IO1_39") (pintype "passive"))
    )
    (net (code "103") (name "unconnected-(IC1-IO45-Pad26)") (class "Default")
      (node (ref "IC1") (pin "26") (pinfunction "IO45_26") (pintype "passive+no_connect"))
    )
    (net (code "104") (name "unconnected-(IC1-IO46-Pad16)") (class "Default")
      (node (ref "IC1") (pin "16") (pinfunction "IO46_16") (pintype "passive+no_connect"))
    )
    (net (code "105") (name "unconnected-(IC1-IO47-Pad24)") (class "Default")
      (node (ref "IC1") (pin "24") (pinfunction "IO47_24") (pintype "passive"))
    )
    (net (code "106") (name "unconnected-(IC2-CELL-Pad4)") (class "Default")
      (node (ref "IC2") (pin "4") (pinfunction "CELL_4") (pintype "passive+no_connect"))
    )
    (net (code "107") (name "unconnected-(IC2-NC-Pad7)") (class "Default")
      (node (ref "IC2") (pin "7") (pinfunction "NC_7") (pintype "passive+no_connect"))
    )
    (net (code "108") (name "unconnected-(IC2-SEL-Pad5)") (class "Default")
      (node (ref "IC2") (pin "5") (pinfunction "SEL_5") (pintype "passive+no_connect"))
    )
    (net (code "109") (name "unconnected-(IC2-~{ACOK}-Pad12)") (class "Default")
      (node (ref "IC2") (pin "12") (pinfunction "~{ACOK}_12") (pintype "passive+no_connect"))
    )
    (net (code "110") (name "unconnected-(IC6-ATTACH-Pad11)") (class "Default")
      (node (ref "IC6") (pin "11") (pinfunction "ATTACH_11") (pintype "passive+no_connect"))
    )
    (net (code "111") (name "unconnected-(IC6-A_B_SIDE-Pad17)") (class "Default")
      (node (ref "IC6") (pin "17") (pinfunction "A_B_SIDE_17") (pintype "passive+no_connect"))
    )
    (net (code "112") (name "unconnected-(IC6-GPIO-Pad15)") (class "Default")
      (node (ref "IC6") (pin "15") (pinfunction "GPIO_15") (pintype "passive+no_connect"))
    )
    (net (code "113") (name "unconnected-(IC6-NC-Pad3)") (class "Default")
      (node (ref "IC6") (pin "3") (pinfunction "NC_3") (pintype "passive+no_connect"))
    )
    (net (code "114") (name "unconnected-(IC6-POWER_OK2-Pad20)") (class "Default")
      (node (ref "IC6") (pin "20") (pinfunction "POWER_OK2_20") (pintype "passive+no_connect"))
    )
    (net (code "115") (name "unconnected-(IC6-POWER_OK3-Pad14)") (class "Default")
      (node (ref "IC6") (pin "14") (pinfunction "POWER_OK3_14") (pintype "passive+no_connect"))
    )
    (net (code "116") (name "unconnected-(IC7-OUT-Pad8)") (class "Default")
      (node (ref "IC7") (pin "8") (pinfunction "OUT_8") (pintype "passive+no_connect"))
    )
    (net (code "117") (name "unconnected-(IC8-COUT-Pad2)") (class "Default")
      (node (ref "IC8") (pin "2") (pinfunction "COUT_2") (pintype "passive+no_connect"))
    )
    (net (code "118") (name "unconnected-(IC8-DOUT-Pad3)") (class "Default")
      (node (ref "IC8") (pin "3") (pinfunction "DOUT_3") (pintype "passive+no_connect"))
    )
    (net (code "119") (name "unconnected-(J2-SBU1-PadA8)") (class "Default")
      (node (ref "J2") (pin "A8") (pinfunction "SBU1_A8") (pintype "bidirectional+no_connect"))
    )
    (net (code "120") (name "unconnected-(J2-SBU2-PadB8)") (class "Default")
      (node (ref "J2") (pin "B8") (pinfunction "SBU2_B8") (pintype "bidirectional+no_connect"))
    )
  )
)
